# RFboardLeiden48_V_0_63.net
KiCad netlist of a schematic drawn in EAGLE
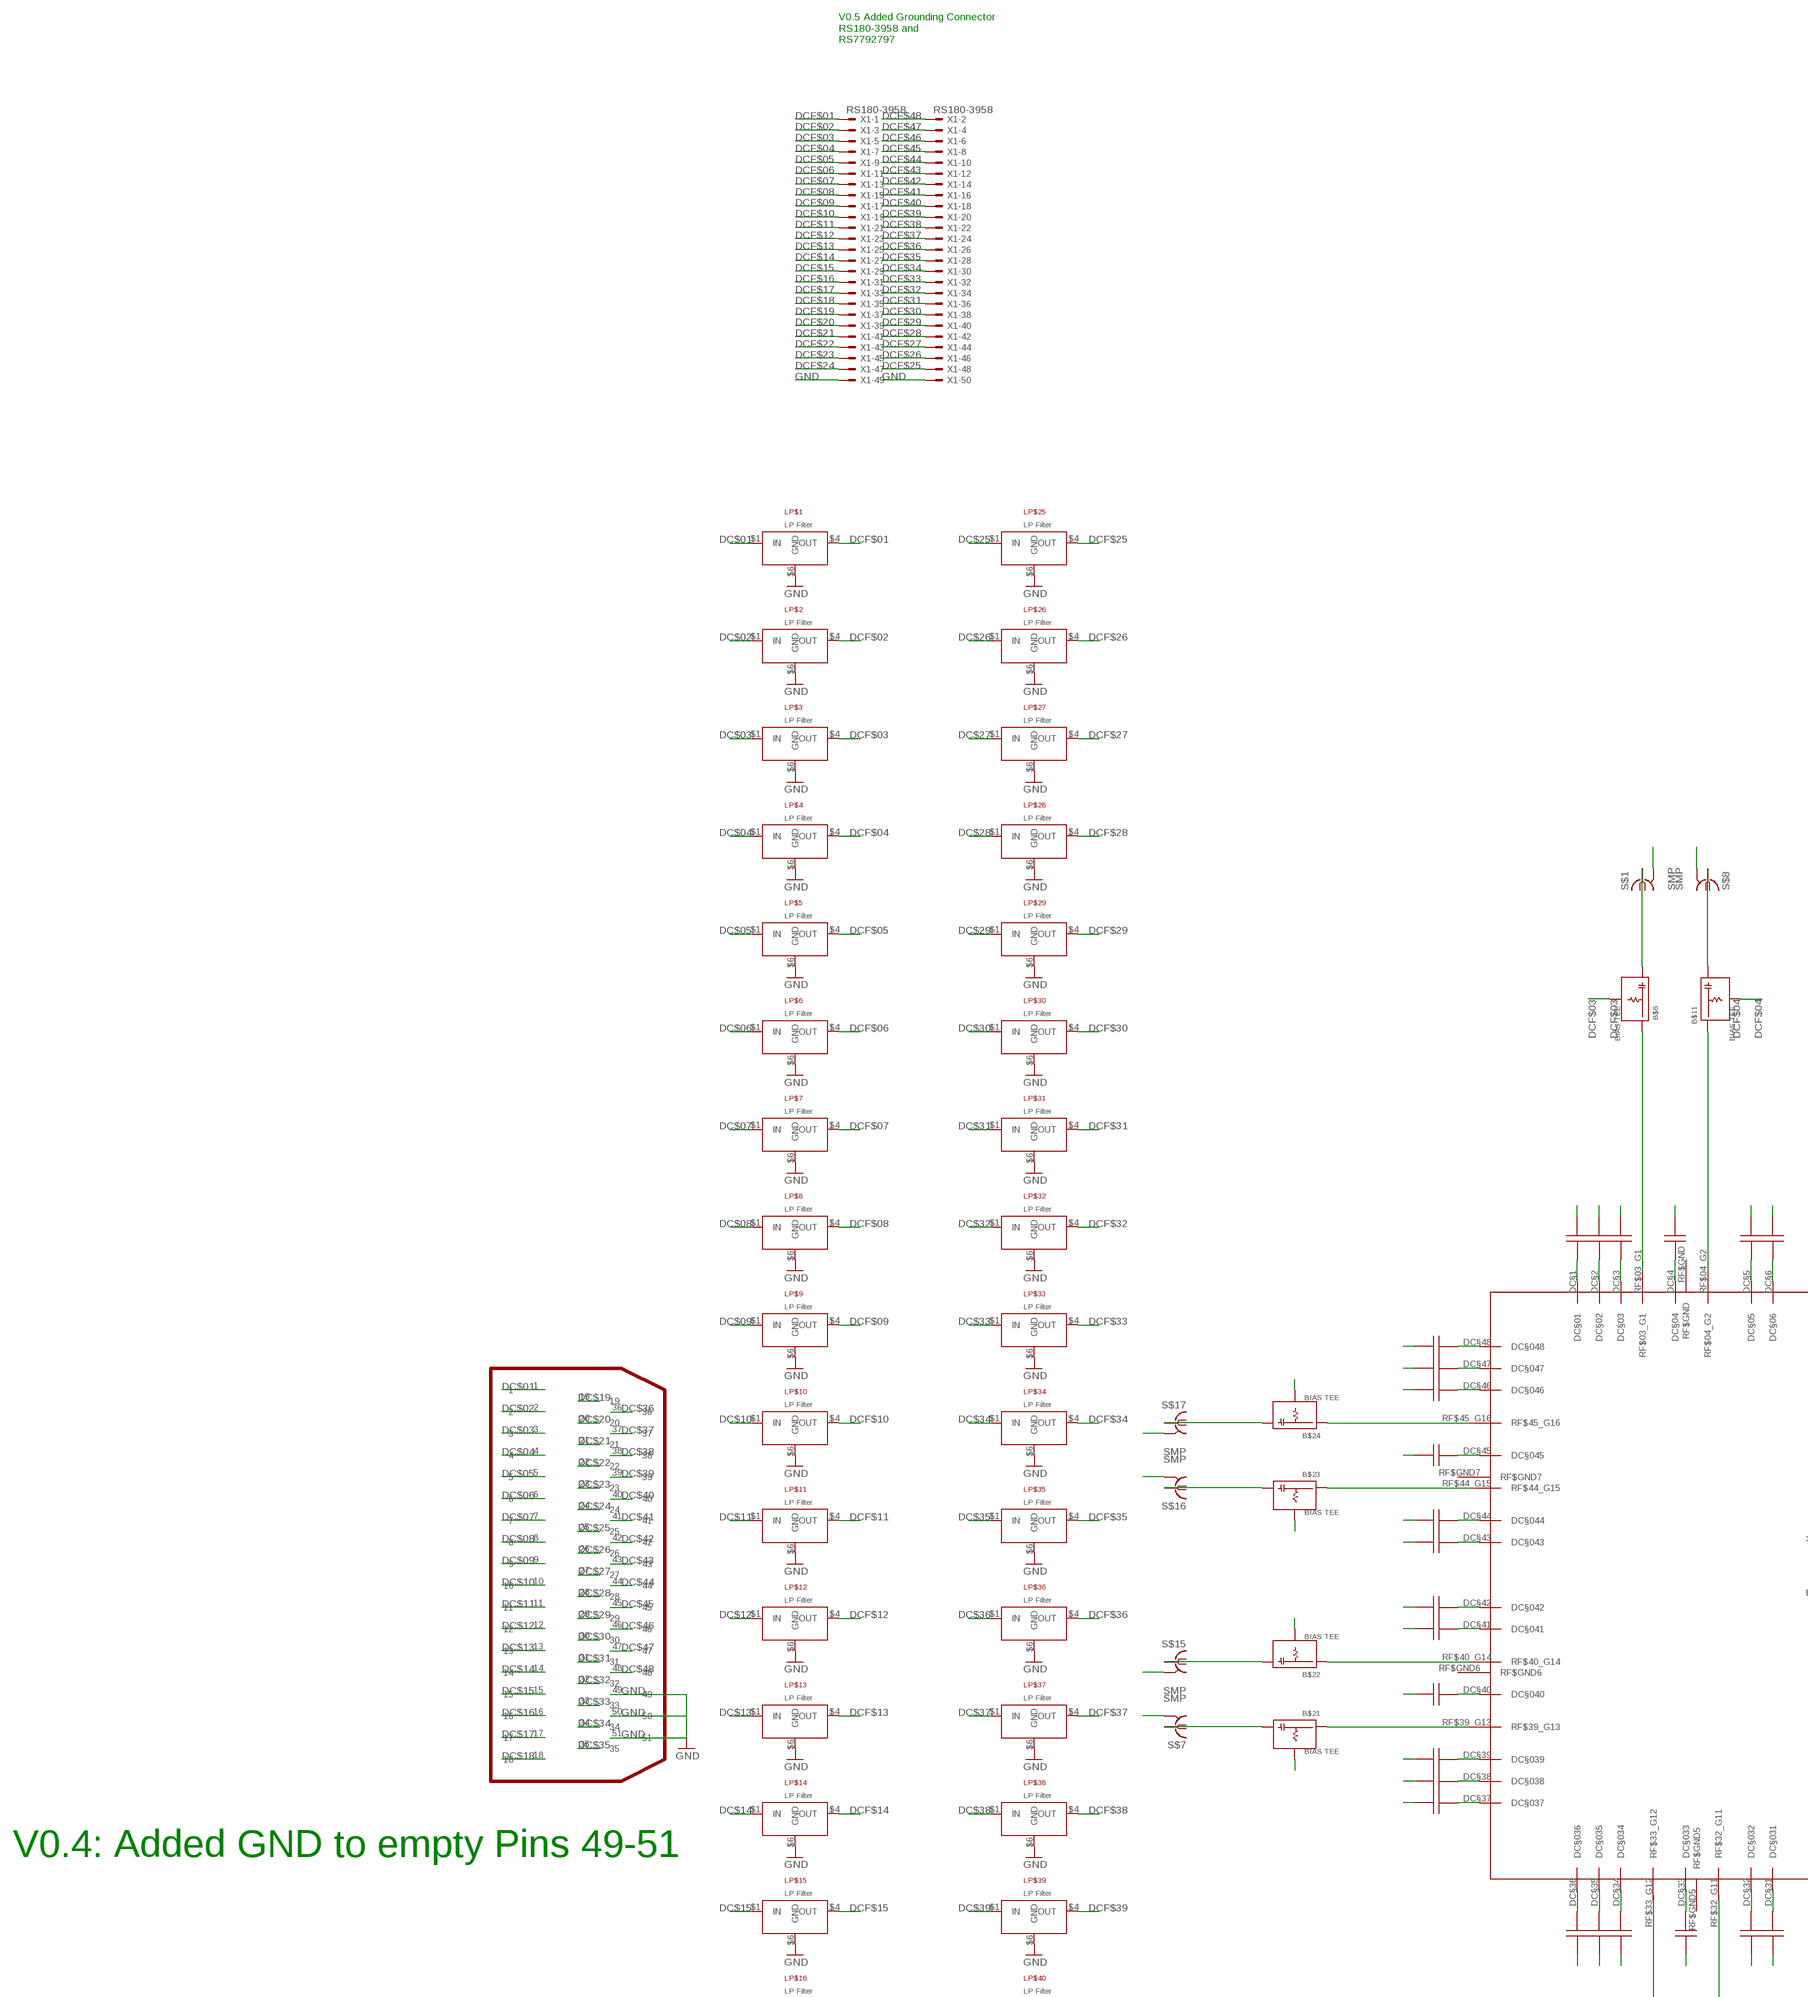
[diagram p0: schematic, sheet 1, part 1 of 3]
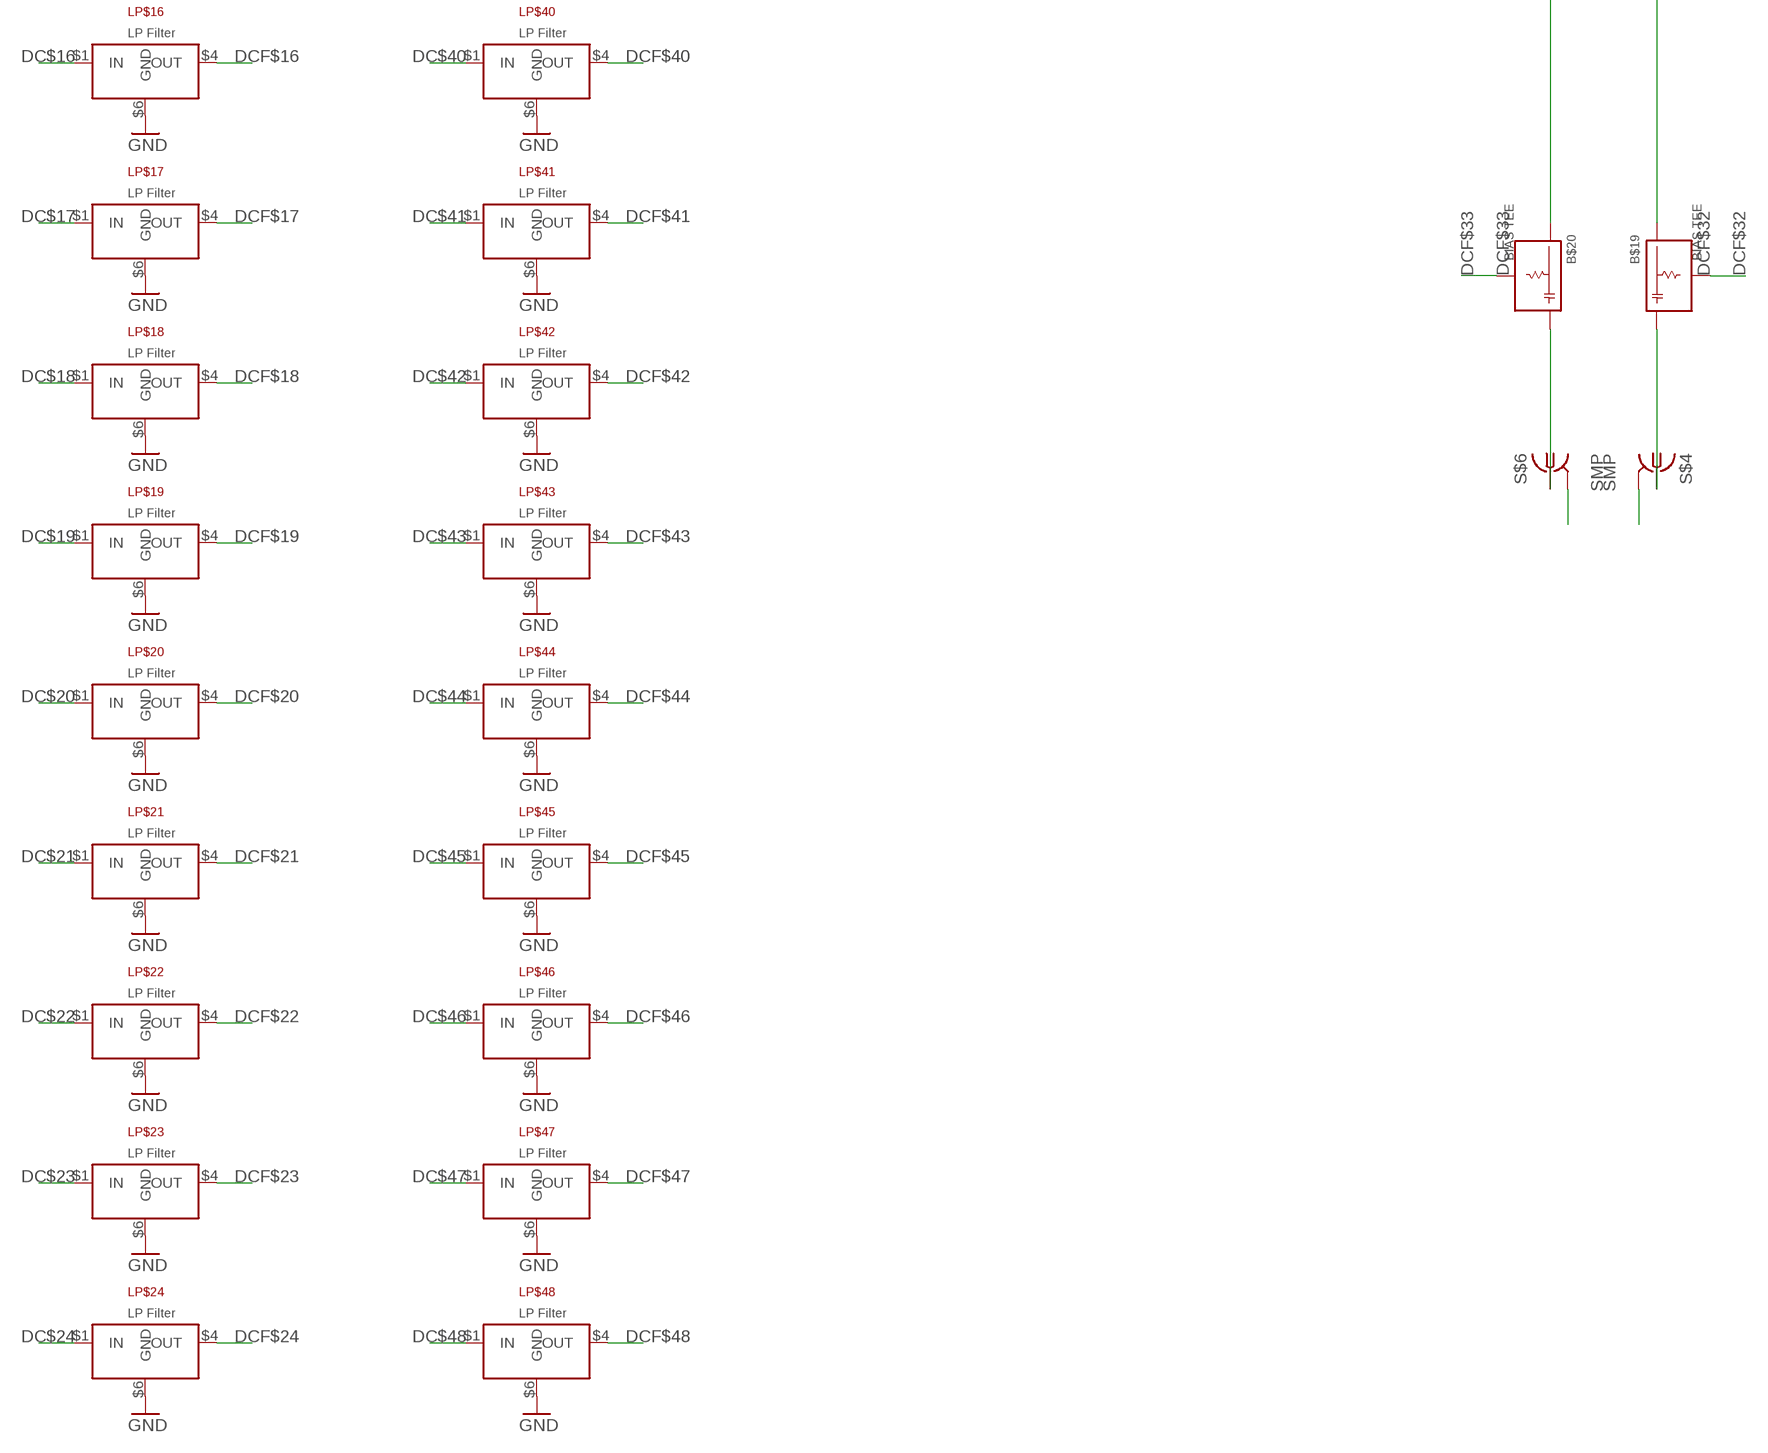
[diagram p1: schematic, sheet 1, part 2 of 3]
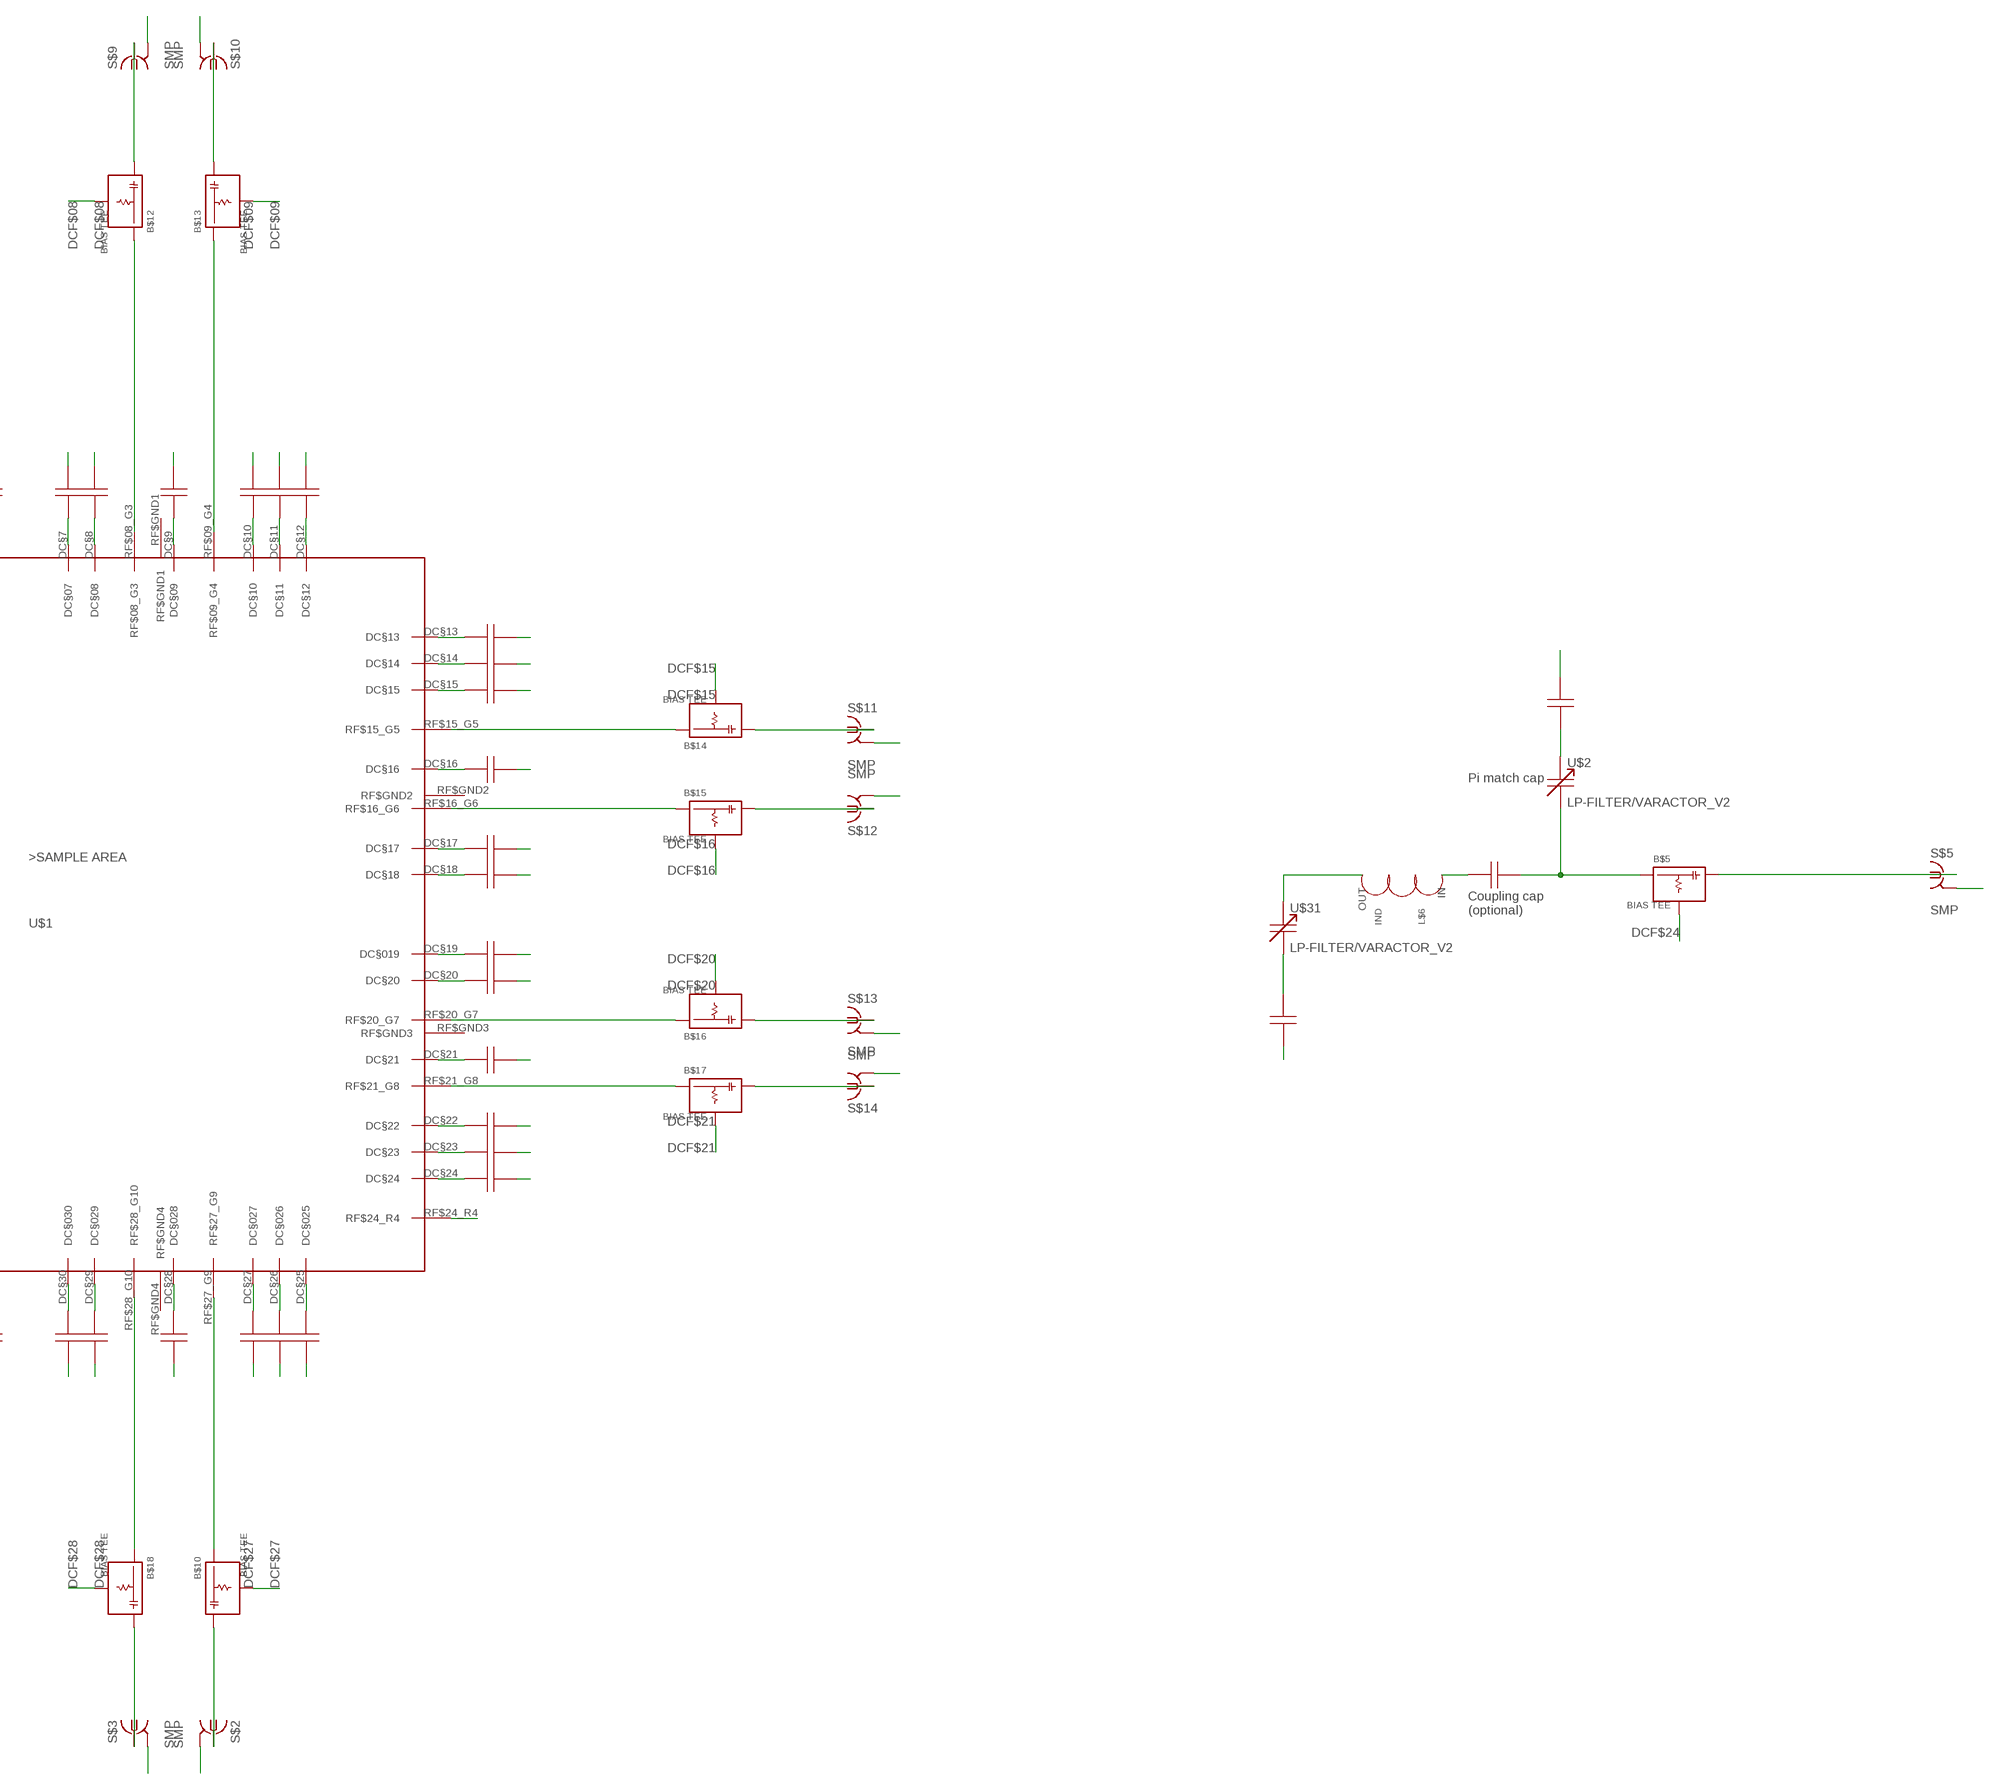
[diagram p2: schematic, sheet 1, part 3 of 3]

(export (version "E")
  (design (tool "Eeschema 10.0.6"))
  (components
    (comp (ref "B$5")
      (value "BIASTEETHINUP")
      (footprint "eagle-import:BIAS_TEE_UP_0603_THIN")
      (libsource (lib "eagle-import") (part "BIASTEETHINUP"))
    )
    (comp (ref "B$6")
      (value "BIASTEEDOWN1")
      (footprint "eagle-import:BIAS_TEE_DOWN_0603")
      (libsource (lib "eagle-import") (part "BIASTEEDOWN1"))
    )
    (comp (ref "B$10")
      (value "BIASTEEDOWN1")
      (footprint "eagle-import:BIAS_TEE_DOWN_0603")
      (libsource (lib "eagle-import") (part "BIASTEEDOWN1"))
    )
    (comp (ref "B$11")
      (value "BIASTEEDOWN1")
      (footprint "eagle-import:BIAS_TEE_DOWN_0603")
      (libsource (lib "eagle-import") (part "BIASTEEDOWN1"))
    )
    (comp (ref "B$12")
      (value "BIASTEEUP1")
      (footprint "eagle-import:BIAS_TEE_UP_0603")
      (libsource (lib "eagle-import") (part "BIASTEEUP1"))
    )
    (comp (ref "B$13")
      (value "BIASTEEUP1")
      (footprint "eagle-import:BIAS_TEE_UP_0603")
      (libsource (lib "eagle-import") (part "BIASTEEUP1"))
    )
    (comp (ref "B$14")
      (value "BIASTEEDOWN1")
      (footprint "eagle-import:BIAS_TEE_DOWN_0603")
      (libsource (lib "eagle-import") (part "BIASTEEDOWN1"))
    )
    (comp (ref "B$15")
      (value "BIASTEEDOWN1")
      (footprint "eagle-import:BIAS_TEE_DOWN_0603")
      (libsource (lib "eagle-import") (part "BIASTEEDOWN1"))
    )
    (comp (ref "B$16")
      (value "BIASTEEUP1")
      (footprint "eagle-import:BIAS_TEE_UP_0603")
      (libsource (lib "eagle-import") (part "BIASTEEUP1"))
    )
    (comp (ref "B$17")
      (value "BIASTEEUP1")
      (footprint "eagle-import:BIAS_TEE_UP_0603")
      (libsource (lib "eagle-import") (part "BIASTEEUP1"))
    )
    (comp (ref "B$18")
      (value "BIASTEEDOWN1")
      (footprint "eagle-import:BIAS_TEE_DOWN_0603")
      (libsource (lib "eagle-import") (part "BIASTEEDOWN1"))
    )
    (comp (ref "B$19")
      (value "BIASTEEUP1")
      (footprint "eagle-import:BIAS_TEE_UP_0603")
      (libsource (lib "eagle-import") (part "BIASTEEUP1"))
    )
    (comp (ref "B$20")
      (value "BIASTEEUP1")
      (footprint "eagle-import:BIAS_TEE_UP_0603")
      (libsource (lib "eagle-import") (part "BIASTEEUP1"))
    )
    (comp (ref "B$21")
      (value "BIASTEEDOWN1")
      (footprint "eagle-import:BIAS_TEE_DOWN_0603")
      (libsource (lib "eagle-import") (part "BIASTEEDOWN1"))
    )
    (comp (ref "B$22")
      (value "BIASTEEDOWN1")
      (footprint "eagle-import:BIAS_TEE_DOWN_0603")
      (libsource (lib "eagle-import") (part "BIASTEEDOWN1"))
    )
    (comp (ref "B$23")
      (value "BIASTEEUP1")
      (footprint "eagle-import:BIAS_TEE_UP_0603")
      (libsource (lib "eagle-import") (part "BIASTEEUP1"))
    )
    (comp (ref "B$24")
      (value "BIASTEEUP1")
      (footprint "eagle-import:BIAS_TEE_UP_0603")
      (libsource (lib "eagle-import") (part "BIASTEEUP1"))
    )
    (comp (ref "L$6")
      (value "L_MATCH")
      (footprint "eagle-import:L_MATCH")
      (libsource (lib "eagle-import") (part "L_MATCH"))
    )
    (comp (ref "LP$1")
      (value "LP-FILTER/1-STAGETOP")
      (footprint "eagle-import:LP-FILTER_1_STAGE_OS_0603_TOP")
      (libsource (lib "eagle-import") (part "LP-FILTER/1-STAGETOP"))
    )
    (comp (ref "LP$2")
      (value "LP-FILTER/1-STAGETOP")
      (footprint "eagle-import:LP-FILTER_1_STAGE_OS_0603_TOP")
      (libsource (lib "eagle-import") (part "LP-FILTER/1-STAGETOP"))
    )
    (comp (ref "LP$3")
      (value "LP-FILTER/1-STAGETOP")
      (footprint "eagle-import:LP-FILTER_1_STAGE_OS_0603_TOP")
      (libsource (lib "eagle-import") (part "LP-FILTER/1-STAGETOP"))
    )
    (comp (ref "LP$4")
      (value "LP-FILTER/1-STAGETOP")
      (footprint "eagle-import:LP-FILTER_1_STAGE_OS_0603_TOP")
      (libsource (lib "eagle-import") (part "LP-FILTER/1-STAGETOP"))
    )
    (comp (ref "LP$5")
      (value "LP-FILTER/1-STAGETOP")
      (footprint "eagle-import:LP-FILTER_1_STAGE_OS_0603_TOP")
      (libsource (lib "eagle-import") (part "LP-FILTER/1-STAGETOP"))
    )
    (comp (ref "LP$6")
      (value "LP-FILTER/1-STAGETOP")
      (footprint "eagle-import:LP-FILTER_1_STAGE_OS_0603_TOP")
      (libsource (lib "eagle-import") (part "LP-FILTER/1-STAGETOP"))
    )
    (comp (ref "LP$7")
      (value "LP-FILTER/1-STAGETOP")
      (footprint "eagle-import:LP-FILTER_1_STAGE_OS_0603_TOP")
      (libsource (lib "eagle-import") (part "LP-FILTER/1-STAGETOP"))
    )
    (comp (ref "LP$8")
      (value "LP-FILTER/1-STAGETOP")
      (footprint "eagle-import:LP-FILTER_1_STAGE_OS_0603_TOP")
      (libsource (lib "eagle-import") (part "LP-FILTER/1-STAGETOP"))
    )
    (comp (ref "LP$9")
      (value "LP-FILTER/1-STAGETOP")
      (footprint "eagle-import:LP-FILTER_1_STAGE_OS_0603_TOP")
      (libsource (lib "eagle-import") (part "LP-FILTER/1-STAGETOP"))
    )
    (comp (ref "LP$10")
      (value "LP-FILTER/1-STAGETOP")
      (footprint "eagle-import:LP-FILTER_1_STAGE_OS_0603_TOP")
      (libsource (lib "eagle-import") (part "LP-FILTER/1-STAGETOP"))
    )
    (comp (ref "LP$11")
      (value "LP-FILTER/1-STAGETOP")
      (footprint "eagle-import:LP-FILTER_1_STAGE_OS_0603_TOP")
      (libsource (lib "eagle-import") (part "LP-FILTER/1-STAGETOP"))
    )
    (comp (ref "LP$12")
      (value "LP-FILTER/1-STAGETOP")
      (footprint "eagle-import:LP-FILTER_1_STAGE_OS_0603_TOP")
      (libsource (lib "eagle-import") (part "LP-FILTER/1-STAGETOP"))
    )
    (comp (ref "LP$13")
      (value "LP-FILTER/1-STAGETOP")
      (footprint "eagle-import:LP-FILTER_1_STAGE_OS_0603_TOP")
      (libsource (lib "eagle-import") (part "LP-FILTER/1-STAGETOP"))
    )
    (comp (ref "LP$14")
      (value "LP-FILTER/1-STAGETOP")
      (footprint "eagle-import:LP-FILTER_1_STAGE_OS_0603_TOP")
      (libsource (lib "eagle-import") (part "LP-FILTER/1-STAGETOP"))
    )
    (comp (ref "LP$15")
      (value "LP-FILTER/1-STAGETOP")
      (footprint "eagle-import:LP-FILTER_1_STAGE_OS_0603_TOP")
      (libsource (lib "eagle-import") (part "LP-FILTER/1-STAGETOP"))
    )
    (comp (ref "LP$16")
      (value "LP-FILTER/1-STAGETOP")
      (footprint "eagle-import:LP-FILTER_1_STAGE_OS_0603_TOP")
      (libsource (lib "eagle-import") (part "LP-FILTER/1-STAGETOP"))
    )
    (comp (ref "LP$17")
      (value "LP-FILTER/1-STAGETOP")
      (footprint "eagle-import:LP-FILTER_1_STAGE_OS_0603_TOP")
      (libsource (lib "eagle-import") (part "LP-FILTER/1-STAGETOP"))
    )
    (comp (ref "LP$18")
      (value "LP-FILTER/1-STAGETOP")
      (footprint "eagle-import:LP-FILTER_1_STAGE_OS_0603_TOP")
      (libsource (lib "eagle-import") (part "LP-FILTER/1-STAGETOP"))
    )
    (comp (ref "LP$19")
      (value "LP-FILTER/1-STAGETOP")
      (footprint "eagle-import:LP-FILTER_1_STAGE_OS_0603_TOP")
      (libsource (lib "eagle-import") (part "LP-FILTER/1-STAGETOP"))
    )
    (comp (ref "LP$20")
      (value "LP-FILTER/1-STAGETOP")
      (footprint "eagle-import:LP-FILTER_1_STAGE_OS_0603_TOP")
      (libsource (lib "eagle-import") (part "LP-FILTER/1-STAGETOP"))
    )
    (comp (ref "LP$21")
      (value "LP-FILTER/1-STAGETOP")
      (footprint "eagle-import:LP-FILTER_1_STAGE_OS_0603_TOP")
      (libsource (lib "eagle-import") (part "LP-FILTER/1-STAGETOP"))
    )
    (comp (ref "LP$22")
      (value "LP-FILTER/1-STAGETOP")
      (footprint "eagle-import:LP-FILTER_1_STAGE_OS_0603_TOP")
      (libsource (lib "eagle-import") (part "LP-FILTER/1-STAGETOP"))
    )
    (comp (ref "LP$23")
      (value "LP-FILTER/1-STAGETOP")
      (footprint "eagle-import:LP-FILTER_1_STAGE_OS_0603_TOP")
      (libsource (lib "eagle-import") (part "LP-FILTER/1-STAGETOP"))
    )
    (comp (ref "LP$24")
      (value "LP-FILTER/1-STAGETOP")
      (footprint "eagle-import:LP-FILTER_1_STAGE_OS_0603_TOP")
      (libsource (lib "eagle-import") (part "LP-FILTER/1-STAGETOP"))
    )
    (comp (ref "LP$25")
      (value "LP-FILTER/1-STAGETOP")
      (footprint "eagle-import:LP-FILTER_1_STAGE_OS_0603_TOP")
      (libsource (lib "eagle-import") (part "LP-FILTER/1-STAGETOP"))
    )
    (comp (ref "LP$26")
      (value "LP-FILTER/1-STAGETOP")
      (footprint "eagle-import:LP-FILTER_1_STAGE_OS_0603_TOP")
      (libsource (lib "eagle-import") (part "LP-FILTER/1-STAGETOP"))
    )
    (comp (ref "LP$27")
      (value "LP-FILTER/1-STAGETOP")
      (footprint "eagle-import:LP-FILTER_1_STAGE_OS_0603_TOP")
      (libsource (lib "eagle-import") (part "LP-FILTER/1-STAGETOP"))
    )
    (comp (ref "LP$28")
      (value "LP-FILTER/1-STAGETOP")
      (footprint "eagle-import:LP-FILTER_1_STAGE_OS_0603_TOP")
      (libsource (lib "eagle-import") (part "LP-FILTER/1-STAGETOP"))
    )
    (comp (ref "LP$29")
      (value "LP-FILTER/1-STAGETOP")
      (footprint "eagle-import:LP-FILTER_1_STAGE_OS_0603_TOP")
      (libsource (lib "eagle-import") (part "LP-FILTER/1-STAGETOP"))
    )
    (comp (ref "LP$30")
      (value "LP-FILTER/1-STAGETOP")
      (footprint "eagle-import:LP-FILTER_1_STAGE_OS_0603_TOP")
      (libsource (lib "eagle-import") (part "LP-FILTER/1-STAGETOP"))
    )
    (comp (ref "LP$31")
      (value "LP-FILTER/1-STAGETOP")
      (footprint "eagle-import:LP-FILTER_1_STAGE_OS_0603_TOP")
      (libsource (lib "eagle-import") (part "LP-FILTER/1-STAGETOP"))
    )
    (comp (ref "LP$32")
      (value "LP-FILTER/1-STAGETOP")
      (footprint "eagle-import:LP-FILTER_1_STAGE_OS_0603_TOP")
      (libsource (lib "eagle-import") (part "LP-FILTER/1-STAGETOP"))
    )
    (comp (ref "LP$33")
      (value "LP-FILTER/1-STAGETOP")
      (footprint "eagle-import:LP-FILTER_1_STAGE_OS_0603_TOP")
      (libsource (lib "eagle-import") (part "LP-FILTER/1-STAGETOP"))
    )
    (comp (ref "LP$34")
      (value "LP-FILTER/1-STAGETOP")
      (footprint "eagle-import:LP-FILTER_1_STAGE_OS_0603_TOP")
      (libsource (lib "eagle-import") (part "LP-FILTER/1-STAGETOP"))
    )
    (comp (ref "LP$35")
      (value "LP-FILTER/1-STAGETOP")
      (footprint "eagle-import:LP-FILTER_1_STAGE_OS_0603_TOP")
      (libsource (lib "eagle-import") (part "LP-FILTER/1-STAGETOP"))
    )
    (comp (ref "LP$36")
      (value "LP-FILTER/1-STAGETOP")
      (footprint "eagle-import:LP-FILTER_1_STAGE_OS_0603_TOP")
      (libsource (lib "eagle-import") (part "LP-FILTER/1-STAGETOP"))
    )
    (comp (ref "LP$37")
      (value "LP-FILTER/1-STAGETOP")
      (footprint "eagle-import:LP-FILTER_1_STAGE_OS_0603_TOP")
      (libsource (lib "eagle-import") (part "LP-FILTER/1-STAGETOP"))
    )
    (comp (ref "LP$38")
      (value "LP-FILTER/1-STAGETOP")
      (footprint "eagle-import:LP-FILTER_1_STAGE_OS_0603_TOP")
      (libsource (lib "eagle-import") (part "LP-FILTER/1-STAGETOP"))
    )
    (comp (ref "LP$39")
      (value "LP-FILTER/1-STAGETOP")
      (footprint "eagle-import:LP-FILTER_1_STAGE_OS_0603_TOP")
      (libsource (lib "eagle-import") (part "LP-FILTER/1-STAGETOP"))
    )
    (comp (ref "LP$40")
      (value "LP-FILTER/1-STAGETOP")
      (footprint "eagle-import:LP-FILTER_1_STAGE_OS_0603_TOP")
      (libsource (lib "eagle-import") (part "LP-FILTER/1-STAGETOP"))
    )
    (comp (ref "LP$41")
      (value "LP-FILTER/1-STAGETOP")
      (footprint "eagle-import:LP-FILTER_1_STAGE_OS_0603_TOP")
      (libsource (lib "eagle-import") (part "LP-FILTER/1-STAGETOP"))
    )
    (comp (ref "LP$42")
      (value "LP-FILTER/1-STAGETOP")
      (footprint "eagle-import:LP-FILTER_1_STAGE_OS_0603_TOP")
      (libsource (lib "eagle-import") (part "LP-FILTER/1-STAGETOP"))
    )
    (comp (ref "LP$43")
      (value "LP-FILTER/1-STAGETOP")
      (footprint "eagle-import:LP-FILTER_1_STAGE_OS_0603_TOP")
      (libsource (lib "eagle-import") (part "LP-FILTER/1-STAGETOP"))
    )
    (comp (ref "LP$44")
      (value "LP-FILTER/1-STAGETOP")
      (footprint "eagle-import:LP-FILTER_1_STAGE_OS_0603_TOP")
      (libsource (lib "eagle-import") (part "LP-FILTER/1-STAGETOP"))
    )
    (comp (ref "LP$45")
      (value "LP-FILTER/1-STAGETOP")
      (footprint "eagle-import:LP-FILTER_1_STAGE_OS_0603_TOP")
      (libsource (lib "eagle-import") (part "LP-FILTER/1-STAGETOP"))
    )
    (comp (ref "LP$46")
      (value "LP-FILTER/1-STAGETOP")
      (footprint "eagle-import:LP-FILTER_1_STAGE_OS_0603_TOP")
      (libsource (lib "eagle-import") (part "LP-FILTER/1-STAGETOP"))
    )
    (comp (ref "LP$47")
      (value "LP-FILTER/1-STAGETOP")
      (footprint "eagle-import:LP-FILTER_1_STAGE_OS_0603_TOP")
      (libsource (lib "eagle-import") (part "LP-FILTER/1-STAGETOP"))
    )
    (comp (ref "LP$48")
      (value "LP-FILTER/1-STAGETOP")
      (footprint "eagle-import:LP-FILTER_1_STAGE_OS_0603_TOP")
      (libsource (lib "eagle-import") (part "LP-FILTER/1-STAGETOP"))
    )
    (comp (ref "S$1")
      (value "MC-921WIDE")
      (footprint "eagle-import:SMP_STRAIGHT_MINI_WIDE")
      (libsource (lib "eagle-import") (part "MC-921WIDE"))
    )
    (comp (ref "S$2")
      (value "MC-921WIDE")
      (footprint "eagle-import:SMP_STRAIGHT_MINI_WIDE")
      (libsource (lib "eagle-import") (part "MC-921WIDE"))
    )
    (comp (ref "S$3")
      (value "MC-921WIDE")
      (footprint "eagle-import:SMP_STRAIGHT_MINI_WIDE")
      (libsource (lib "eagle-import") (part "MC-921WIDE"))
    )
    (comp (ref "S$4")
      (value "MC-921WIDE")
      (footprint "eagle-import:SMP_STRAIGHT_MINI_WIDE")
      (libsource (lib "eagle-import") (part "MC-921WIDE"))
    )
    (comp (ref "S$5")
      (value "MC-921")
      (footprint "eagle-import:SMP_STRAIGHT_MINI_WIDE_V1_01_ROUND")
      (libsource (lib "eagle-import") (part "MC-921"))
    )
    (comp (ref "S$6")
      (value "MC-921WIDE")
      (footprint "eagle-import:SMP_STRAIGHT_MINI_WIDE")
      (libsource (lib "eagle-import") (part "MC-921WIDE"))
    )
    (comp (ref "S$7")
      (value "MC-921WIDE")
      (footprint "eagle-import:SMP_STRAIGHT_MINI_WIDE")
      (libsource (lib "eagle-import") (part "MC-921WIDE"))
    )
    (comp (ref "S$8")
      (value "MC-921WIDE")
      (footprint "eagle-import:SMP_STRAIGHT_MINI_WIDE")
      (libsource (lib "eagle-import") (part "MC-921WIDE"))
    )
    (comp (ref "S$9")
      (value "MC-921WIDE")
      (footprint "eagle-import:SMP_STRAIGHT_MINI_WIDE")
      (libsource (lib "eagle-import") (part "MC-921WIDE"))
    )
    (comp (ref "S$10")
      (value "MC-921WIDE")
      (footprint "eagle-import:SMP_STRAIGHT_MINI_WIDE")
      (libsource (lib "eagle-import") (part "MC-921WIDE"))
    )
    (comp (ref "S$11")
      (value "MC-921WIDE")
      (footprint "eagle-import:SMP_STRAIGHT_MINI_WIDE")
      (libsource (lib "eagle-import") (part "MC-921WIDE"))
    )
    (comp (ref "S$12")
      (value "MC-921WIDE")
      (footprint "eagle-import:SMP_STRAIGHT_MINI_WIDE")
      (libsource (lib "eagle-import") (part "MC-921WIDE"))
    )
    (comp (ref "S$13")
      (value "MC-921WIDE")
      (footprint "eagle-import:SMP_STRAIGHT_MINI_WIDE")
      (libsource (lib "eagle-import") (part "MC-921WIDE"))
    )
    (comp (ref "S$14")
      (value "MC-921WIDE")
      (footprint "eagle-import:SMP_STRAIGHT_MINI_WIDE")
      (libsource (lib "eagle-import") (part "MC-921WIDE"))
    )
    (comp (ref "S$15")
      (value "MC-921WIDE")
      (footprint "eagle-import:SMP_STRAIGHT_MINI_WIDE")
      (libsource (lib "eagle-import") (part "MC-921WIDE"))
    )
    (comp (ref "S$16")
      (value "MC-921WIDE")
      (footprint "eagle-import:SMP_STRAIGHT_MINI_WIDE")
      (libsource (lib "eagle-import") (part "MC-921WIDE"))
    )
    (comp (ref "S$17")
      (value "MC-921WIDE")
      (footprint "eagle-import:SMP_STRAIGHT_MINI_WIDE")
      (libsource (lib "eagle-import") (part "MC-921WIDE"))
    )
    (comp (ref "U$1")
      (value "48DC+24RF_V4.0")
      (footprint "eagle-import:48DC+24RF_V4.0")
      (libsource (lib "eagle-import") (part "48DC+24RF_V4.0"))
    )
    (comp (ref "U$2")
      (value "LP-FILTER/VARACTOR_V2")
      (footprint "eagle-import:LP-FILTER_VARACTOR_V2")
      (libsource (lib "eagle-import") (part "LP-FILTER/VARACTOR_V2"))
    )
    (comp (ref "U$3")
      (value "LP-FILTER/CAPACITOR/0603NORMAL")
      (footprint "eagle-import:LP-FILTER_CAPACITOR_0603_BOTTOM_V2")
      (libsource (lib "eagle-import") (part "LP-FILTER/CAPACITOR/0603NORMAL"))
    )
    (comp (ref "U$25")
      (value "51_PIN_M83513/11-G")
      (footprint "eagle-import:51_PIN_M83513_11-G")
      (libsource (lib "eagle-import") (part "51_PIN_M83513/11-G"))
    )
    (comp (ref "U$31")
      (value "LP-FILTER/VARACTOR_V2")
      (footprint "eagle-import:LP-FILTER_VARACTOR_V2")
      (libsource (lib "eagle-import") (part "LP-FILTER/VARACTOR_V2"))
    )
    (comp (ref "U$32")
      (value "LP-FILTER/CAPACITOR/0603NORMAL")
      (footprint "eagle-import:LP-FILTER_CAPACITOR_0603_BOTTOM_V2")
      (libsource (lib "eagle-import") (part "LP-FILTER/CAPACITOR/0603NORMAL"))
    )
    (comp (ref "U$33")
      (value "LP-FILTER/CAPACITOR/0603THIN")
      (footprint "eagle-import:LP-FILTER_CAPACITOR_0603_BOTTOM")
      (libsource (lib "eagle-import") (part "LP-FILTER/CAPACITOR/0603THIN"))
    )
    (comp (ref "U$42")
      (value "LP-FILTER/CAPACITOR/0603THIN")
      (footprint "eagle-import:LP-FILTER_CAPACITOR_0603_BOTTOM")
      (libsource (lib "eagle-import") (part "LP-FILTER/CAPACITOR/0603THIN"))
    )
    (comp (ref "U$43")
      (value "LP-FILTER/CAPACITOR/0603THIN")
      (footprint "eagle-import:LP-FILTER_CAPACITOR_0603_BOTTOM")
      (libsource (lib "eagle-import") (part "LP-FILTER/CAPACITOR/0603THIN"))
    )
    (comp (ref "U$44")
      (value "LP-FILTER/CAPACITOR/0603THIN")
      (footprint "eagle-import:LP-FILTER_CAPACITOR_0603_BOTTOM")
      (libsource (lib "eagle-import") (part "LP-FILTER/CAPACITOR/0603THIN"))
    )
    (comp (ref "U$45")
      (value "LP-FILTER/CAPACITOR/0603THIN")
      (footprint "eagle-import:LP-FILTER_CAPACITOR_0603_BOTTOM")
      (libsource (lib "eagle-import") (part "LP-FILTER/CAPACITOR/0603THIN"))
    )
    (comp (ref "U$46")
      (value "LP-FILTER/CAPACITOR/0603THIN")
      (footprint "eagle-import:LP-FILTER_CAPACITOR_0603_BOTTOM")
      (libsource (lib "eagle-import") (part "LP-FILTER/CAPACITOR/0603THIN"))
    )
    (comp (ref "U$47")
      (value "LP-FILTER/CAPACITOR/0603THIN")
      (footprint "eagle-import:LP-FILTER_CAPACITOR_0603_BOTTOM")
      (libsource (lib "eagle-import") (part "LP-FILTER/CAPACITOR/0603THIN"))
    )
    (comp (ref "U$48")
      (value "LP-FILTER/CAPACITOR/0603THIN")
      (footprint "eagle-import:LP-FILTER_CAPACITOR_0603_BOTTOM")
      (libsource (lib "eagle-import") (part "LP-FILTER/CAPACITOR/0603THIN"))
    )
    (comp (ref "U$49")
      (value "LP-FILTER/CAPACITOR/0603THIN")
      (footprint "eagle-import:LP-FILTER_CAPACITOR_0603_BOTTOM")
      (libsource (lib "eagle-import") (part "LP-FILTER/CAPACITOR/0603THIN"))
    )
    (comp (ref "U$50")
      (value "LP-FILTER/CAPACITOR/0603THIN")
      (footprint "eagle-import:LP-FILTER_CAPACITOR_0603_BOTTOM")
      (libsource (lib "eagle-import") (part "LP-FILTER/CAPACITOR/0603THIN"))
    )
    (comp (ref "U$51")
      (value "LP-FILTER/CAPACITOR/0603THIN")
      (footprint "eagle-import:LP-FILTER_CAPACITOR_0603_BOTTOM")
      (libsource (lib "eagle-import") (part "LP-FILTER/CAPACITOR/0603THIN"))
    )
    (comp (ref "U$52")
      (value "LP-FILTER/CAPACITOR/0603THIN")
      (footprint "eagle-import:LP-FILTER_CAPACITOR_0603_BOTTOM")
      (libsource (lib "eagle-import") (part "LP-FILTER/CAPACITOR/0603THIN"))
    )
    (comp (ref "U$53")
      (value "LP-FILTER/CAPACITOR/0603THIN")
      (footprint "eagle-import:LP-FILTER_CAPACITOR_0603_BOTTOM")
      (libsource (lib "eagle-import") (part "LP-FILTER/CAPACITOR/0603THIN"))
    )
    (comp (ref "U$54")
      (value "LP-FILTER/CAPACITOR/0603THIN")
      (footprint "eagle-import:LP-FILTER_CAPACITOR_0603_BOTTOM")
      (libsource (lib "eagle-import") (part "LP-FILTER/CAPACITOR/0603THIN"))
    )
    (comp (ref "U$55")
      (value "LP-FILTER/CAPACITOR/0603THIN")
      (footprint "eagle-import:LP-FILTER_CAPACITOR_0603_BOTTOM")
      (libsource (lib "eagle-import") (part "LP-FILTER/CAPACITOR/0603THIN"))
    )
    (comp (ref "U$56")
      (value "LP-FILTER/CAPACITOR/0603THIN")
      (footprint "eagle-import:LP-FILTER_CAPACITOR_0603_BOTTOM")
      (libsource (lib "eagle-import") (part "LP-FILTER/CAPACITOR/0603THIN"))
    )
    (comp (ref "U$57")
      (value "LP-FILTER/CAPACITOR/0603THIN")
      (footprint "eagle-import:LP-FILTER_CAPACITOR_0603_BOTTOM")
      (libsource (lib "eagle-import") (part "LP-FILTER/CAPACITOR/0603THIN"))
    )
    (comp (ref "U$58")
      (value "LP-FILTER/CAPACITOR/0603THIN")
      (footprint "eagle-import:LP-FILTER_CAPACITOR_0603_BOTTOM")
      (libsource (lib "eagle-import") (part "LP-FILTER/CAPACITOR/0603THIN"))
    )
    (comp (ref "U$59")
      (value "LP-FILTER/CAPACITOR/0603THIN")
      (footprint "eagle-import:LP-FILTER_CAPACITOR_0603_BOTTOM")
      (libsource (lib "eagle-import") (part "LP-FILTER/CAPACITOR/0603THIN"))
    )
    (comp (ref "U$60")
      (value "LP-FILTER/CAPACITOR/0603THIN")
      (footprint "eagle-import:LP-FILTER_CAPACITOR_0603_BOTTOM")
      (libsource (lib "eagle-import") (part "LP-FILTER/CAPACITOR/0603THIN"))
    )
    (comp (ref "U$61")
      (value "LP-FILTER/CAPACITOR/0603THIN")
      (footprint "eagle-import:LP-FILTER_CAPACITOR_0603_BOTTOM")
      (libsource (lib "eagle-import") (part "LP-FILTER/CAPACITOR/0603THIN"))
    )
    (comp (ref "U$62")
      (value "LP-FILTER/CAPACITOR/0603THIN")
      (footprint "eagle-import:LP-FILTER_CAPACITOR_0603_BOTTOM")
      (libsource (lib "eagle-import") (part "LP-FILTER/CAPACITOR/0603THIN"))
    )
    (comp (ref "U$63")
      (value "LP-FILTER/CAPACITOR/0603THIN")
      (footprint "eagle-import:LP-FILTER_CAPACITOR_0603_BOTTOM")
      (libsource (lib "eagle-import") (part "LP-FILTER/CAPACITOR/0603THIN"))
    )
    (comp (ref "U$64")
      (value "LP-FILTER/CAPACITOR/0603THIN")
      (footprint "eagle-import:LP-FILTER_CAPACITOR_0603_BOTTOM")
      (libsource (lib "eagle-import") (part "LP-FILTER/CAPACITOR/0603THIN"))
    )
    (comp (ref "U$65")
      (value "LP-FILTER/CAPACITOR/0603THIN")
      (footprint "eagle-import:LP-FILTER_CAPACITOR_0603_BOTTOM")
      (libsource (lib "eagle-import") (part "LP-FILTER/CAPACITOR/0603THIN"))
    )
    (comp (ref "U$66")
      (value "LP-FILTER/CAPACITOR/0603THIN")
      (footprint "eagle-import:LP-FILTER_CAPACITOR_0603_BOTTOM")
      (libsource (lib "eagle-import") (part "LP-FILTER/CAPACITOR/0603THIN"))
    )
    (comp (ref "U$67")
      (value "LP-FILTER/CAPACITOR/0603THIN")
      (footprint "eagle-import:LP-FILTER_CAPACITOR_0603_BOTTOM")
      (libsource (lib "eagle-import") (part "LP-FILTER/CAPACITOR/0603THIN"))
    )
    (comp (ref "U$68")
      (value "LP-FILTER/CAPACITOR/0603THIN")
      (footprint "eagle-import:LP-FILTER_CAPACITOR_0603_BOTTOM")
      (libsource (lib "eagle-import") (part "LP-FILTER/CAPACITOR/0603THIN"))
    )
    (comp (ref "U$69")
      (value "LP-FILTER/CAPACITOR/0603THIN")
      (footprint "eagle-import:LP-FILTER_CAPACITOR_0603_BOTTOM")
      (libsource (lib "eagle-import") (part "LP-FILTER/CAPACITOR/0603THIN"))
    )
    (comp (ref "U$70")
      (value "LP-FILTER/CAPACITOR/0603THIN")
      (footprint "eagle-import:LP-FILTER_CAPACITOR_0603_BOTTOM")
      (libsource (lib "eagle-import") (part "LP-FILTER/CAPACITOR/0603THIN"))
    )
    (comp (ref "U$71")
      (value "LP-FILTER/CAPACITOR/0603THIN")
      (footprint "eagle-import:LP-FILTER_CAPACITOR_0603_BOTTOM")
      (libsource (lib "eagle-import") (part "LP-FILTER/CAPACITOR/0603THIN"))
    )
    (comp (ref "U$72")
      (value "LP-FILTER/CAPACITOR/0603THIN")
      (footprint "eagle-import:LP-FILTER_CAPACITOR_0603_BOTTOM")
      (libsource (lib "eagle-import") (part "LP-FILTER/CAPACITOR/0603THIN"))
    )
    (comp (ref "U$73")
      (value "LP-FILTER/CAPACITOR/0603THIN")
      (footprint "eagle-import:LP-FILTER_CAPACITOR_0603_BOTTOM")
      (libsource (lib "eagle-import") (part "LP-FILTER/CAPACITOR/0603THIN"))
    )
    (comp (ref "U$74")
      (value "LP-FILTER/CAPACITOR/0603THIN")
      (footprint "eagle-import:LP-FILTER_CAPACITOR_0603_BOTTOM")
      (libsource (lib "eagle-import") (part "LP-FILTER/CAPACITOR/0603THIN"))
    )
    (comp (ref "U$75")
      (value "LP-FILTER/CAPACITOR/0603THIN")
      (footprint "eagle-import:LP-FILTER_CAPACITOR_0603_BOTTOM")
      (libsource (lib "eagle-import") (part "LP-FILTER/CAPACITOR/0603THIN"))
    )
    (comp (ref "U$76")
      (value "LP-FILTER/CAPACITOR/0603THIN")
      (footprint "eagle-import:LP-FILTER_CAPACITOR_0603_BOTTOM")
      (libsource (lib "eagle-import") (part "LP-FILTER/CAPACITOR/0603THIN"))
    )
    (comp (ref "U$77")
      (value "LP-FILTER/CAPACITOR/0603THIN")
      (footprint "eagle-import:LP-FILTER_CAPACITOR_0603_BOTTOM")
      (libsource (lib "eagle-import") (part "LP-FILTER/CAPACITOR/0603THIN"))
    )
    (comp (ref "U$78")
      (value "LP-FILTER/CAPACITOR/0603THIN")
      (footprint "eagle-import:LP-FILTER_CAPACITOR_0603_BOTTOM")
      (libsource (lib "eagle-import") (part "LP-FILTER/CAPACITOR/0603THIN"))
    )
    (comp (ref "U$79")
      (value "LP-FILTER/CAPACITOR/0603THIN")
      (footprint "eagle-import:LP-FILTER_CAPACITOR_0603_BOTTOM")
      (libsource (lib "eagle-import") (part "LP-FILTER/CAPACITOR/0603THIN"))
    )
    (comp (ref "U$80")
      (value "LP-FILTER/CAPACITOR/0603THIN")
      (footprint "eagle-import:LP-FILTER_CAPACITOR_0603_BOTTOM")
      (libsource (lib "eagle-import") (part "LP-FILTER/CAPACITOR/0603THIN"))
    )
    (comp (ref "U$81")
      (value "LP-FILTER/CAPACITOR/0603THIN")
      (footprint "eagle-import:LP-FILTER_CAPACITOR_0603_BOTTOM")
      (libsource (lib "eagle-import") (part "LP-FILTER/CAPACITOR/0603THIN"))
    )
    (comp (ref "U$82")
      (value "LP-FILTER/CAPACITOR/0603THIN")
      (footprint "eagle-import:LP-FILTER_CAPACITOR_0603_BOTTOM")
      (libsource (lib "eagle-import") (part "LP-FILTER/CAPACITOR/0603THIN"))
    )
    (comp (ref "U$83")
      (value "LP-FILTER/CAPACITOR/0603THIN")
      (footprint "eagle-import:LP-FILTER_CAPACITOR_0603_BOTTOM")
      (libsource (lib "eagle-import") (part "LP-FILTER/CAPACITOR/0603THIN"))
    )
    (comp (ref "U$84")
      (value "LP-FILTER/CAPACITOR/0603THIN")
      (footprint "eagle-import:LP-FILTER_CAPACITOR_0603_BOTTOM")
      (libsource (lib "eagle-import") (part "LP-FILTER/CAPACITOR/0603THIN"))
    )
    (comp (ref "U$85")
      (value "LP-FILTER/CAPACITOR/0603THIN")
      (footprint "eagle-import:LP-FILTER_CAPACITOR_0603_BOTTOM")
      (libsource (lib "eagle-import") (part "LP-FILTER/CAPACITOR/0603THIN"))
    )
    (comp (ref "U$86")
      (value "LP-FILTER/CAPACITOR/0603THIN")
      (footprint "eagle-import:LP-FILTER_CAPACITOR_0603_BOTTOM")
      (libsource (lib "eagle-import") (part "LP-FILTER/CAPACITOR/0603THIN"))
    )
    (comp (ref "U$87")
      (value "LP-FILTER/CAPACITOR/0603THIN")
      (footprint "eagle-import:LP-FILTER_CAPACITOR_0603_BOTTOM")
      (libsource (lib "eagle-import") (part "LP-FILTER/CAPACITOR/0603THIN"))
    )
    (comp (ref "U$88")
      (value "LP-FILTER/CAPACITOR/0603THIN")
      (footprint "eagle-import:LP-FILTER_CAPACITOR_0603_BOTTOM")
      (libsource (lib "eagle-import") (part "LP-FILTER/CAPACITOR/0603THIN"))
    )
    (comp (ref "U$89")
      (value "LP-FILTER/CAPACITOR/0603THIN")
      (footprint "eagle-import:LP-FILTER_CAPACITOR_0603_BOTTOM")
      (libsource (lib "eagle-import") (part "LP-FILTER/CAPACITOR/0603THIN"))
    )
    (comp (ref "X1")
      (value "RS180-3958")
      (footprint "eagle-import:SMDSMALL87758-5016")
      (libsource (lib "eagle-import") (part "87758-5016"))
    )
  )
  (nets
    (net (code "1") (name "/DC$01") (class "Default")
      (node (ref "LP$1") (pin "$1") (pinfunction "IN_$1") (pintype "bidirectional"))
      (node (ref "U$25") (pin "1") (pinfunction "1_1") (pintype "bidirectional"))
    )
    (net (code "2") (name "/DC$02") (class "Default")
      (node (ref "LP$2") (pin "$1") (pinfunction "IN_$1") (pintype "bidirectional"))
      (node (ref "U$25") (pin "2") (pinfunction "2_2") (pintype "bidirectional"))
    )
    (net (code "3") (name "/DC$03") (class "Default")
      (node (ref "LP$3") (pin "$1") (pinfunction "IN_$1") (pintype "bidirectional"))
      (node (ref "U$25") (pin "3") (pinfunction "3_3") (pintype "bidirectional"))
    )
    (net (code "4") (name "/DC$04") (class "Default")
      (node (ref "LP$4") (pin "$1") (pinfunction "IN_$1") (pintype "bidirectional"))
      (node (ref "U$25") (pin "4") (pinfunction "4_4") (pintype "bidirectional"))
    )
    (net (code "5") (name "/DC$05") (class "Default")
      (node (ref "LP$5") (pin "$1") (pinfunction "IN_$1") (pintype "bidirectional"))
      (node (ref "U$25") (pin "5") (pinfunction "5_5") (pintype "bidirectional"))
    )
    (net (code "6") (name "/DC$06") (class "Default")
      (node (ref "LP$6") (pin "$1") (pinfunction "IN_$1") (pintype "bidirectional"))
      (node (ref "U$25") (pin "6") (pinfunction "6_6") (pintype "bidirectional"))
    )
    (net (code "7") (name "/DC$07") (class "Default")
      (node (ref "LP$7") (pin "$1") (pinfunction "IN_$1") (pintype "bidirectional"))
      (node (ref "U$25") (pin "7") (pinfunction "7_7") (pintype "bidirectional"))
    )
    (net (code "8") (name "/DC$08") (class "Default")
      (node (ref "LP$8") (pin "$1") (pinfunction "IN_$1") (pintype "bidirectional"))
      (node (ref "U$25") (pin "8") (pinfunction "8_8") (pintype "bidirectional"))
    )
    (net (code "9") (name "/DC$09") (class "Default")
      (node (ref "LP$9") (pin "$1") (pinfunction "IN_$1") (pintype "bidirectional"))
      (node (ref "U$25") (pin "9") (pinfunction "9_9") (pintype "bidirectional"))
    )
    (net (code "10") (name "/DC$10") (class "Default")
      (node (ref "LP$10") (pin "$1") (pinfunction "IN_$1") (pintype "bidirectional"))
      (node (ref "U$25") (pin "10") (pinfunction "10_10") (pintype "bidirectional"))
    )
    (net (code "11") (name "/DC$11") (class "Default")
      (node (ref "LP$11") (pin "$1") (pinfunction "IN_$1") (pintype "bidirectional"))
      (node (ref "U$25") (pin "11") (pinfunction "11_11") (pintype "bidirectional"))
    )
    (net (code "12") (name "/DC$12") (class "Default")
      (node (ref "LP$12") (pin "$1") (pinfunction "IN_$1") (pintype "bidirectional"))
      (node (ref "U$25") (pin "12") (pinfunction "12_12") (pintype "bidirectional"))
    )
    (net (code "13") (name "/DC$13") (class "Default")
      (node (ref "LP$13") (pin "$1") (pinfunction "IN_$1") (pintype "bidirectional"))
      (node (ref "U$25") (pin "13") (pinfunction "13_13") (pintype "bidirectional"))
    )
    (net (code "14") (name "/DC$14") (class "Default")
      (node (ref "LP$14") (pin "$1") (pinfunction "IN_$1") (pintype "bidirectional"))
      (node (ref "U$25") (pin "14") (pinfunction "14_14") (pintype "bidirectional"))
    )
    (net (code "15") (name "/DC$15") (class "Default")
      (node (ref "LP$15") (pin "$1") (pinfunction "IN_$1") (pintype "bidirectional"))
      (node (ref "U$25") (pin "15") (pinfunction "15_15") (pintype "bidirectional"))
    )
    (net (code "16") (name "/DC$16") (class "Default")
      (node (ref "LP$16") (pin "$1") (pinfunction "IN_$1") (pintype "bidirectional"))
      (node (ref "U$25") (pin "16") (pinfunction "16_16") (pintype "bidirectional"))
    )
    (net (code "17") (name "/DC$17") (class "Default")
      (node (ref "LP$17") (pin "$1") (pinfunction "IN_$1") (pintype "bidirectional"))
      (node (ref "U$25") (pin "17") (pinfunction "17_17") (pintype "bidirectional"))
    )
    (net (code "18") (name "/DC$18") (class "Default")
      (node (ref "LP$18") (pin "$1") (pinfunction "IN_$1") (pintype "bidirectional"))
      (node (ref "U$25") (pin "18") (pinfunction "18_18") (pintype "bidirectional"))
    )
    (net (code "19") (name "/DC$19") (class "Default")
      (node (ref "LP$19") (pin "$1") (pinfunction "IN_$1") (pintype "bidirectional"))
      (node (ref "U$25") (pin "19") (pinfunction "19_19") (pintype "bidirectional"))
    )
    (net (code "20") (name "/DC$20") (class "Default")
      (node (ref "LP$20") (pin "$1") (pinfunction "IN_$1") (pintype "bidirectional"))
      (node (ref "U$25") (pin "20") (pinfunction "20_20") (pintype "bidirectional"))
    )
    (net (code "21") (name "/DC$21") (class "Default")
      (node (ref "LP$21") (pin "$1") (pinfunction "IN_$1") (pintype "bidirectional"))
      (node (ref "U$25") (pin "21") (pinfunction "21_21") (pintype "bidirectional"))
    )
    (net (code "22") (name "/DC$22") (class "Default")
      (node (ref "LP$22") (pin "$1") (pinfunction "IN_$1") (pintype "bidirectional"))
      (node (ref "U$25") (pin "22") (pinfunction "22_22") (pintype "bidirectional"))
    )
    (net (code "23") (name "/DC$23") (class "Default")
      (node (ref "LP$23") (pin "$1") (pinfunction "IN_$1") (pintype "bidirectional"))
      (node (ref "U$25") (pin "23") (pinfunction "23_23") (pintype "bidirectional"))
    )
    (net (code "24") (name "/DC$24") (class "Default")
      (node (ref "LP$24") (pin "$1") (pinfunction "IN_$1") (pintype "bidirectional"))
      (node (ref "U$25") (pin "24") (pinfunction "24_24") (pintype "bidirectional"))
    )
    (net (code "25") (name "/DC$25") (class "Default")
      (node (ref "LP$25") (pin "$1") (pinfunction "IN_$1") (pintype "bidirectional"))
      (node (ref "U$25") (pin "25") (pinfunction "25_25") (pintype "bidirectional"))
    )
    (net (code "26") (name "/DC$26") (class "Default")
      (node (ref "LP$26") (pin "$1") (pinfunction "IN_$1") (pintype "bidirectional"))
      (node (ref "U$25") (pin "26") (pinfunction "26_26") (pintype "bidirectional"))
    )
    (net (code "27") (name "/DC$27") (class "Default")
      (node (ref "LP$27") (pin "$1") (pinfunction "IN_$1") (pintype "bidirectional"))
      (node (ref "U$25") (pin "27") (pinfunction "27_27") (pintype "bidirectional"))
    )
    (net (code "28") (name "/DC$28") (class "Default")
      (node (ref "LP$28") (pin "$1") (pinfunction "IN_$1") (pintype "bidirectional"))
      (node (ref "U$25") (pin "28") (pinfunction "28_28") (pintype "bidirectional"))
    )
    (net (code "29") (name "/DC$29") (class "Default")
      (node (ref "LP$29") (pin "$1") (pinfunction "IN_$1") (pintype "bidirectional"))
      (node (ref "U$25") (pin "29") (pinfunction "29_29") (pintype "bidirectional"))
    )
    (net (code "30") (name "/DC$30") (class "Default")
      (node (ref "LP$30") (pin "$1") (pinfunction "IN_$1") (pintype "bidirectional"))
      (node (ref "U$25") (pin "30") (pinfunction "30_30") (pintype "bidirectional"))
    )
    (net (code "31") (name "/DC$31") (class "Default")
      (node (ref "LP$31") (pin "$1") (pinfunction "IN_$1") (pintype "bidirectional"))
      (node (ref "U$25") (pin "31") (pinfunction "31_31") (pintype "bidirectional"))
    )
    (net (code "32") (name "/DC$32") (class "Default")
      (node (ref "LP$32") (pin "$1") (pinfunction "IN_$1") (pintype "bidirectional"))
      (node (ref "U$25") (pin "32") (pinfunction "32_32") (pintype "bidirectional"))
    )
    (net (code "33") (name "/DC$33") (class "Default")
      (node (ref "LP$33") (pin "$1") (pinfunction "IN_$1") (pintype "bidirectional"))
      (node (ref "U$25") (pin "33") (pinfunction "33_33") (pintype "bidirectional"))
    )
    (net (code "34") (name "/DC$34") (class "Default")
      (node (ref "LP$34") (pin "$1") (pinfunction "IN_$1") (pintype "bidirectional"))
      (node (ref "U$25") (pin "34") (pinfunction "34_34") (pintype "bidirectional"))
    )
    (net (code "35") (name "/DC$35") (class "Default")
      (node (ref "LP$35") (pin "$1") (pinfunction "IN_$1") (pintype "bidirectional"))
      (node (ref "U$25") (pin "35") (pinfunction "35_35") (pintype "bidirectional"))
    )
    (net (code "36") (name "/DC$36") (class "Default")
      (node (ref "LP$36") (pin "$1") (pinfunction "IN_$1") (pintype "bidirectional"))
      (node (ref "U$25") (pin "36") (pinfunction "36_36") (pintype "bidirectional"))
    )
    (net (code "37") (name "/DC$37") (class "Default")
      (node (ref "LP$37") (pin "$1") (pinfunction "IN_$1") (pintype "bidirectional"))
      (node (ref "U$25") (pin "37") (pinfunction "37_37") (pintype "bidirectional"))
    )
    (net (code "38") (name "/DC$38") (class "Default")
      (node (ref "LP$38") (pin "$1") (pinfunction "IN_$1") (pintype "bidirectional"))
      (node (ref "U$25") (pin "38") (pinfunction "38_38") (pintype "bidirectional"))
    )
    (net (code "39") (name "/DC$39") (class "Default")
      (node (ref "LP$39") (pin "$1") (pinfunction "IN_$1") (pintype "bidirectional"))
      (node (ref "U$25") (pin "39") (pinfunction "39_39") (pintype "bidirectional"))
    )
    (net (code "40") (name "/DC$40") (class "Default")
      (node (ref "LP$40") (pin "$1") (pinfunction "IN_$1") (pintype "bidirectional"))
      (node (ref "U$25") (pin "40") (pinfunction "40_40") (pintype "bidirectional"))
    )
    (net (code "41") (name "/DC$41") (class "Default")
      (node (ref "LP$41") (pin "$1") (pinfunction "IN_$1") (pintype "bidirectional"))
      (node (ref "U$25") (pin "41") (pinfunction "41_41") (pintype "bidirectional"))
    )
    (net (code "42") (name "/DC$42") (class "Default")
      (node (ref "LP$42") (pin "$1") (pinfunction "IN_$1") (pintype "bidirectional"))
      (node (ref "U$25") (pin "42") (pinfunction "42_42") (pintype "bidirectional"))
    )
    (net (code "43") (name "/DC$43") (class "Default")
      (node (ref "LP$43") (pin "$1") (pinfunction "IN_$1") (pintype "bidirectional"))
      (node (ref "U$25") (pin "43") (pinfunction "43_43") (pintype "bidirectional"))
    )
    (net (code "44") (name "/DC$44") (class "Default")
      (node (ref "LP$44") (pin "$1") (pinfunction "IN_$1") (pintype "bidirectional"))
      (node (ref "U$25") (pin "44") (pinfunction "44_44") (pintype "bidirectional"))
    )
    (net (code "45") (name "/DC$45") (class "Default")
      (node (ref "LP$45") (pin "$1") (pinfunction "IN_$1") (pintype "bidirectional"))
      (node (ref "U$25") (pin "45") (pinfunction "45_45") (pintype "bidirectional"))
    )
    (net (code "46") (name "/DC$46") (class "Default")
      (node (ref "LP$46") (pin "$1") (pinfunction "IN_$1") (pintype "bidirectional"))
      (node (ref "U$25") (pin "46") (pinfunction "46_46") (pintype "bidirectional"))
    )
    (net (code "47") (name "/DC$47") (class "Default")
      (node (ref "LP$47") (pin "$1") (pinfunction "IN_$1") (pintype "bidirectional"))
      (node (ref "U$25") (pin "47") (pinfunction "47_47") (pintype "bidirectional"))
    )
    (net (code "48") (name "/DC$48") (class "Default")
      (node (ref "LP$48") (pin "$1") (pinfunction "IN_$1") (pintype "bidirectional"))
      (node (ref "U$25") (pin "48") (pinfunction "48_48") (pintype "bidirectional"))
    )
    (net (code "49") (name "/DCF$01") (class "Default")
      (node (ref "LP$1") (pin "$4") (pinfunction "OUT_$4") (pintype "bidirectional"))
      (node (ref "U$1") (pin "DC§1") (pinfunction "DC§01_DC§1") (pintype "bidirectional"))
      (node (ref "U$42") (pin "OUT") (pinfunction "2_OUT") (pintype "passive"))
      (node (ref "X1") (pin "P$1") (pinfunction "S_P$1") (pintype "passive"))
    )
    (net (code "50") (name "/DCF$02") (class "Default")
      (node (ref "LP$2") (pin "$4") (pinfunction "OUT_$4") (pintype "bidirectional"))
      (node (ref "U$1") (pin "DC§2") (pinfunction "DC§02_DC§2") (pintype "bidirectional"))
      (node (ref "U$43") (pin "OUT") (pinfunction "2_OUT") (pintype "passive"))
      (node (ref "X1") (pin "P$3") (pinfunction "S_P$3") (pintype "passive"))
    )
    (net (code "51") (name "/DCF$03") (class "Default")
      (node (ref "B$6") (pin "LF") (pinfunction "LF_LF") (pintype "bidirectional"))
      (node (ref "LP$3") (pin "$4") (pinfunction "OUT_$4") (pintype "bidirectional"))
      (node (ref "U$1") (pin "DC§3") (pinfunction "DC§03_DC§3") (pintype "bidirectional"))
      (node (ref "U$44") (pin "OUT") (pinfunction "2_OUT") (pintype "passive"))
      (node (ref "X1") (pin "P$5") (pinfunction "S_P$5") (pintype "passive"))
    )
    (net (code "52") (name "/DCF$04") (class "Default")
      (node (ref "B$11") (pin "LF") (pinfunction "LF_LF") (pintype "bidirectional"))
      (node (ref "LP$4") (pin "$4") (pinfunction "OUT_$4") (pintype "bidirectional"))
      (node (ref "U$1") (pin "DC§4") (pinfunction "DC§04_DC§4") (pintype "bidirectional"))
      (node (ref "U$45") (pin "OUT") (pinfunction "2_OUT") (pintype "passive"))
      (node (ref "X1") (pin "P$7") (pinfunction "S_P$7") (pintype "passive"))
    )
    (net (code "53") (name "/DCF$05") (class "Default")
      (node (ref "LP$5") (pin "$4") (pinfunction "OUT_$4") (pintype "bidirectional"))
      (node (ref "U$1") (pin "DC§5") (pinfunction "DC§05_DC§5") (pintype "bidirectional"))
      (node (ref "U$46") (pin "OUT") (pinfunction "2_OUT") (pintype "passive"))
      (node (ref "X1") (pin "P$9") (pinfunction "S_P$9") (pintype "passive"))
    )
    (net (code "54") (name "/DCF$06") (class "Default")
      (node (ref "LP$6") (pin "$4") (pinfunction "OUT_$4") (pintype "bidirectional"))
      (node (ref "U$1") (pin "DC§6") (pinfunction "DC§06_DC§6") (pintype "bidirectional"))
      (node (ref "U$47") (pin "OUT") (pinfunction "2_OUT") (pintype "passive"))
      (node (ref "X1") (pin "P$11") (pinfunction "S_P$11") (pintype "passive"))
    )
    (net (code "55") (name "/DCF$07") (class "Default")
      (node (ref "LP$7") (pin "$4") (pinfunction "OUT_$4") (pintype "bidirectional"))
      (node (ref "U$1") (pin "DC§7") (pinfunction "DC§07_DC§7") (pintype "bidirectional"))
      (node (ref "U$48") (pin "OUT") (pinfunction "2_OUT") (pintype "passive"))
      (node (ref "X1") (pin "P$13") (pinfunction "S_P$13") (pintype "passive"))
    )
    (net (code "56") (name "/DCF$08") (class "Default")
      (node (ref "B$12") (pin "LF") (pinfunction "LF_LF") (pintype "bidirectional"))
      (node (ref "LP$8") (pin "$4") (pinfunction "OUT_$4") (pintype "bidirectional"))
      (node (ref "U$1") (pin "DC§8") (pinfunction "DC§08_DC§8") (pintype "bidirectional"))
      (node (ref "U$49") (pin "OUT") (pinfunction "2_OUT") (pintype "passive"))
      (node (ref "X1") (pin "P$15") (pinfunction "S_P$15") (pintype "passive"))
    )
    (net (code "57") (name "/DCF$09") (class "Default")
      (node (ref "B$13") (pin "LF") (pinfunction "LF_LF") (pintype "bidirectional"))
      (node (ref "LP$9") (pin "$4") (pinfunction "OUT_$4") (pintype "bidirectional"))
      (node (ref "U$1") (pin "DC§9") (pinfunction "DC§09_DC§9") (pintype "bidirectional"))
      (node (ref "U$50") (pin "OUT") (pinfunction "2_OUT") (pintype "passive"))
      (node (ref "X1") (pin "P$17") (pinfunction "S_P$17") (pintype "passive"))
    )
    (net (code "58") (name "/DCF$10") (class "Default")
      (node (ref "LP$10") (pin "$4") (pinfunction "OUT_$4") (pintype "bidirectional"))
      (node (ref "U$1") (pin "DC§10") (pinfunction "DC§10_DC§10") (pintype "bidirectional"))
      (node (ref "U$51") (pin "OUT") (pinfunction "2_OUT") (pintype "passive"))
      (node (ref "X1") (pin "P$19") (pinfunction "S_P$19") (pintype "passive"))
    )
    (net (code "59") (name "/DCF$11") (class "Default")
      (node (ref "LP$11") (pin "$4") (pinfunction "OUT_$4") (pintype "bidirectional"))
      (node (ref "U$1") (pin "DC§11") (pinfunction "DC§11_DC§11") (pintype "bidirectional"))
      (node (ref "U$52") (pin "OUT") (pinfunction "2_OUT") (pintype "passive"))
      (node (ref "X1") (pin "P$21") (pinfunction "S_P$21") (pintype "passive"))
    )
    (net (code "60") (name "/DCF$12") (class "Default")
      (node (ref "LP$12") (pin "$4") (pinfunction "OUT_$4") (pintype "bidirectional"))
      (node (ref "U$1") (pin "DC§12") (pinfunction "DC§12_DC§12") (pintype "bidirectional"))
      (node (ref "U$53") (pin "OUT") (pinfunction "2_OUT") (pintype "passive"))
      (node (ref "X1") (pin "P$23") (pinfunction "S_P$23") (pintype "passive"))
    )
    (net (code "61") (name "/DCF$13") (class "Default")
      (node (ref "LP$13") (pin "$4") (pinfunction "OUT_$4") (pintype "bidirectional"))
      (node (ref "U$1") (pin "DC§13") (pinfunction "DC§13_DC§13") (pintype "bidirectional"))
      (node (ref "U$54") (pin "IN") (pinfunction "1_IN") (pintype "passive"))
      (node (ref "X1") (pin "P$25") (pinfunction "S_P$25") (pintype "passive"))
    )
    (net (code "62") (name "/DCF$14") (class "Default")
      (node (ref "LP$14") (pin "$4") (pinfunction "OUT_$4") (pintype "bidirectional"))
      (node (ref "U$1") (pin "DC§14") (pinfunction "DC§14_DC§14") (pintype "bidirectional"))
      (node (ref "U$55") (pin "IN") (pinfunction "1_IN") (pintype "passive"))
      (node (ref "X1") (pin "P$27") (pinfunction "S_P$27") (pintype "passive"))
    )
    (net (code "63") (name "/DCF$15") (class "Default")
      (node (ref "B$14") (pin "LF") (pinfunction "LF_LF") (pintype "bidirectional"))
      (node (ref "LP$15") (pin "$4") (pinfunction "OUT_$4") (pintype "bidirectional"))
      (node (ref "U$1") (pin "DC§15") (pinfunction "DC§15_DC§15") (pintype "bidirectional"))
      (node (ref "U$56") (pin "IN") (pinfunction "1_IN") (pintype "passive"))
      (node (ref "X1") (pin "P$29") (pinfunction "S_P$29") (pintype "passive"))
    )
    (net (code "64") (name "/DCF$16") (class "Default")
      (node (ref "B$15") (pin "LF") (pinfunction "LF_LF") (pintype "bidirectional"))
      (node (ref "LP$16") (pin "$4") (pinfunction "OUT_$4") (pintype "bidirectional"))
      (node (ref "U$1") (pin "DC§16") (pinfunction "DC§16_DC§16") (pintype "bidirectional"))
      (node (ref "U$57") (pin "IN") (pinfunction "1_IN") (pintype "passive"))
      (node (ref "X1") (pin "P$31") (pinfunction "S_P$31") (pintype "passive"))
    )
    (net (code "65") (name "/DCF$17") (class "Default")
      (node (ref "LP$17") (pin "$4") (pinfunction "OUT_$4") (pintype "bidirectional"))
      (node (ref "U$1") (pin "DC§17") (pinfunction "DC§17_DC§17") (pintype "bidirectional"))
      (node (ref "U$58") (pin "IN") (pinfunction "1_IN") (pintype "passive"))
      (node (ref "X1") (pin "P$33") (pinfunction "S_P$33") (pintype "passive"))
    )
    (net (code "66") (name "/DCF$18") (class "Default")
      (node (ref "LP$18") (pin "$4") (pinfunction "OUT_$4") (pintype "bidirectional"))
      (node (ref "U$1") (pin "DC§18") (pinfunction "DC§18_DC§18") (pintype "bidirectional"))
      (node (ref "U$59") (pin "IN") (pinfunction "1_IN") (pintype "passive"))
      (node (ref "X1") (pin "P$35") (pinfunction "S_P$35") (pintype "passive"))
    )
    (net (code "67") (name "/DCF$19") (class "Default")
      (node (ref "LP$19") (pin "$4") (pinfunction "OUT_$4") (pintype "bidirectional"))
      (node (ref "U$1") (pin "DC§19") (pinfunction "DC§019_DC§19") (pintype "bidirectional"))
      (node (ref "U$60") (pin "IN") (pinfunction "1_IN") (pintype "passive"))
      (node (ref "X1") (pin "P$37") (pinfunction "S_P$37") (pintype "passive"))
    )
    (net (code "68") (name "/DCF$20") (class "Default")
      (node (ref "B$16") (pin "LF") (pinfunction "LF_LF") (pintype "bidirectional"))
      (node (ref "LP$20") (pin "$4") (pinfunction "OUT_$4") (pintype "bidirectional"))
      (node (ref "U$1") (pin "DC§20") (pinfunction "DC§20_DC§20") (pintype "bidirectional"))
      (node (ref "U$61") (pin "IN") (pinfunction "1_IN") (pintype "passive"))
      (node (ref "X1") (pin "P$39") (pinfunction "S_P$39") (pintype "passive"))
    )
    (net (code "69") (name "/DCF$21") (class "Default")
      (node (ref "B$17") (pin "LF") (pinfunction "LF_LF") (pintype "bidirectional"))
      (node (ref "LP$21") (pin "$4") (pinfunction "OUT_$4") (pintype "bidirectional"))
      (node (ref "U$1") (pin "DC§21") (pinfunction "DC§21_DC§21") (pintype "bidirectional"))
      (node (ref "U$62") (pin "IN") (pinfunction "1_IN") (pintype "passive"))
      (node (ref "X1") (pin "P$41") (pinfunction "S_P$41") (pintype "passive"))
    )
    (net (code "70") (name "/DCF$22") (class "Default")
      (node (ref "LP$22") (pin "$4") (pinfunction "OUT_$4") (pintype "bidirectional"))
      (node (ref "U$1") (pin "DC§22") (pinfunction "DC§22_DC§22") (pintype "bidirectional"))
      (node (ref "U$63") (pin "IN") (pinfunction "1_IN") (pintype "passive"))
      (node (ref "X1") (pin "P$43") (pinfunction "S_P$43") (pintype "passive"))
    )
    (net (code "71") (name "/DCF$23") (class "Default")
      (node (ref "LP$23") (pin "$4") (pinfunction "OUT_$4") (pintype "bidirectional"))
      (node (ref "U$1") (pin "DC§23") (pinfunction "DC§23_DC§23") (pintype "bidirectional"))
      (node (ref "U$64") (pin "IN") (pinfunction "1_IN") (pintype "passive"))
      (node (ref "X1") (pin "P$45") (pinfunction "S_P$45") (pintype "passive"))
    )
    (net (code "72") (name "/DCF$24") (class "Default")
      (node (ref "B$5") (pin "LF") (pinfunction "LF_LF") (pintype "bidirectional"))
      (node (ref "LP$24") (pin "$4") (pinfunction "OUT_$4") (pintype "bidirectional"))
      (node (ref "U$1") (pin "DC§24") (pinfunction "DC§24_DC§24") (pintype "bidirectional"))
      (node (ref "U$65") (pin "IN") (pinfunction "1_IN") (pintype "passive"))
      (node (ref "X1") (pin "P$47") (pinfunction "S_P$47") (pintype "passive"))
    )
    (net (code "73") (name "/DCF$25") (class "Default")
      (node (ref "LP$25") (pin "$4") (pinfunction "OUT_$4") (pintype "bidirectional"))
      (node (ref "U$1") (pin "DC§25") (pinfunction "DC§025_DC§25") (pintype "bidirectional"))
      (node (ref "U$31") (pin "OUT1") (pinfunction "2_OUT1") (pintype "passive"))
      (node (ref "U$32") (pin "OUT") (pinfunction "2_OUT") (pintype "passive"))
      (node (ref "U$66") (pin "IN") (pinfunction "1_IN") (pintype "passive"))
      (node (ref "X1") (pin "P$48") (pinfunction "S_P$48") (pintype "passive"))
    )
    (net (code "74") (name "/DCF$26") (class "Default")
      (node (ref "LP$26") (pin "$4") (pinfunction "OUT_$4") (pintype "bidirectional"))
      (node (ref "U$1") (pin "DC§26") (pinfunction "DC§026_DC§26") (pintype "bidirectional"))
      (node (ref "U$2") (pin "OUT") (pinfunction "1_OUT") (pintype "passive"))
      (node (ref "U$3") (pin "IN") (pinfunction "1_IN") (pintype "passive"))
      (node (ref "U$67") (pin "IN") (pinfunction "1_IN") (pintype "passive"))
      (node (ref "X1") (pin "P$46") (pinfunction "S_P$46") (pintype "passive"))
    )
    (net (code "75") (name "/DCF$27") (class "Default")
      (node (ref "B$10") (pin "LF") (pinfunction "LF_LF") (pintype "bidirectional"))
      (node (ref "LP$27") (pin "$4") (pinfunction "OUT_$4") (pintype "bidirectional"))
      (node (ref "U$1") (pin "DC§27") (pinfunction "DC§027_DC§27") (pintype "bidirectional"))
      (node (ref "U$68") (pin "IN") (pinfunction "1_IN") (pintype "passive"))
      (node (ref "X1") (pin "P$44") (pinfunction "S_P$44") (pintype "passive"))
    )
    (net (code "76") (name "/DCF$28") (class "Default")
      (node (ref "B$18") (pin "LF") (pinfunction "LF_LF") (pintype "bidirectional"))
      (node (ref "LP$28") (pin "$4") (pinfunction "OUT_$4") (pintype "bidirectional"))
      (node (ref "U$1") (pin "DC§28") (pinfunction "DC§028_DC§28") (pintype "bidirectional"))
      (node (ref "U$69") (pin "IN") (pinfunction "1_IN") (pintype "passive"))
      (node (ref "X1") (pin "P$42") (pinfunction "S_P$42") (pintype "passive"))
    )
    (net (code "77") (name "/DCF$29") (class "Default")
      (node (ref "LP$29") (pin "$4") (pinfunction "OUT_$4") (pintype "bidirectional"))
      (node (ref "U$1") (pin "DC§29") (pinfunction "DC§029_DC§29") (pintype "bidirectional"))
      (node (ref "U$70") (pin "IN") (pinfunction "1_IN") (pintype "passive"))
      (node (ref "X1") (pin "P$40") (pinfunction "S_P$40") (pintype "passive"))
    )
    (net (code "78") (name "/DCF$30") (class "Default")
      (node (ref "LP$30") (pin "$4") (pinfunction "OUT_$4") (pintype "bidirectional"))
      (node (ref "U$1") (pin "DC§30") (pinfunction "DC§030_DC§30") (pintype "bidirectional"))
      (node (ref "U$71") (pin "IN") (pinfunction "1_IN") (pintype "passive"))
      (node (ref "X1") (pin "P$38") (pinfunction "S_P$38") (pintype "passive"))
    )
    (net (code "79") (name "/DCF$31") (class "Default")
      (node (ref "LP$31") (pin "$4") (pinfunction "OUT_$4") (pintype "bidirectional"))
      (node (ref "U$1") (pin "DC§31") (pinfunction "DC§031_DC§31") (pintype "bidirectional"))
      (node (ref "U$72") (pin "IN") (pinfunction "1_IN") (pintype "passive"))
      (node (ref "X1") (pin "P$36") (pinfunction "S_P$36") (pintype "passive"))
    )
    (net (code "80") (name "/DCF$32") (class "Default")
      (node (ref "B$19") (pin "LF") (pinfunction "LF_LF") (pintype "bidirectional"))
      (node (ref "LP$32") (pin "$4") (pinfunction "OUT_$4") (pintype "bidirectional"))
      (node (ref "U$1") (pin "DC§32") (pinfunction "DC§032_DC§32") (pintype "bidirectional"))
      (node (ref "U$73") (pin "IN") (pinfunction "1_IN") (pintype "passive"))
      (node (ref "X1") (pin "P$34") (pinfunction "S_P$34") (pintype "passive"))
    )
    (net (code "81") (name "/DCF$33") (class "Default")
      (node (ref "B$20") (pin "LF") (pinfunction "LF_LF") (pintype "bidirectional"))
      (node (ref "LP$33") (pin "$4") (pinfunction "OUT_$4") (pintype "bidirectional"))
      (node (ref "U$1") (pin "DC§33") (pinfunction "DC§033_DC§33") (pintype "bidirectional"))
      (node (ref "U$74") (pin "IN") (pinfunction "1_IN") (pintype "passive"))
      (node (ref "X1") (pin "P$32") (pinfunction "S_P$32") (pintype "passive"))
    )
    (net (code "82") (name "/DCF$34") (class "Default")
      (node (ref "LP$34") (pin "$4") (pinfunction "OUT_$4") (pintype "bidirectional"))
      (node (ref "U$1") (pin "DC§34") (pinfunction "DC§034_DC§34") (pintype "bidirectional"))
      (node (ref "U$75") (pin "IN") (pinfunction "1_IN") (pintype "passive"))
      (node (ref "X1") (pin "P$30") (pinfunction "S_P$30") (pintype "passive"))
    )
    (net (code "83") (name "/DCF$35") (class "Default")
      (node (ref "LP$35") (pin "$4") (pinfunction "OUT_$4") (pintype "bidirectional"))
      (node (ref "U$1") (pin "DC§35") (pinfunction "DC§035_DC§35") (pintype "bidirectional"))
      (node (ref "U$76") (pin "IN") (pinfunction "1_IN") (pintype "passive"))
      (node (ref "X1") (pin "P$28") (pinfunction "S_P$28") (pintype "passive"))
    )
    (net (code "84") (name "/DCF$36") (class "Default")
      (node (ref "LP$36") (pin "$4") (pinfunction "OUT_$4") (pintype "bidirectional"))
      (node (ref "U$1") (pin "DC§36") (pinfunction "DC§036_DC§36") (pintype "bidirectional"))
      (node (ref "U$77") (pin "IN") (pinfunction "1_IN") (pintype "passive"))
      (node (ref "X1") (pin "P$26") (pinfunction "S_P$26") (pintype "passive"))
    )
    (net (code "85") (name "/DCF$37") (class "Default")
      (node (ref "LP$37") (pin "$4") (pinfunction "OUT_$4") (pintype "bidirectional"))
      (node (ref "U$1") (pin "DC§37") (pinfunction "DC§037_DC§37") (pintype "bidirectional"))
      (node (ref "U$78") (pin "IN") (pinfunction "1_IN") (pintype "passive"))
      (node (ref "X1") (pin "P$24") (pinfunction "S_P$24") (pintype "passive"))
    )
    (net (code "86") (name "/DCF$38") (class "Default")
      (node (ref "LP$38") (pin "$4") (pinfunction "OUT_$4") (pintype "bidirectional"))
      (node (ref "U$1") (pin "DC§38") (pinfunction "DC§038_DC§38") (pintype "bidirectional"))
      (node (ref "U$79") (pin "IN") (pinfunction "1_IN") (pintype "passive"))
      (node (ref "X1") (pin "P$22") (pinfunction "S_P$22") (pintype "passive"))
    )
    (net (code "87") (name "/DCF$39") (class "Default")
      (node (ref "B$21") (pin "LF") (pinfunction "LF_LF") (pintype "bidirectional"))
      (node (ref "LP$39") (pin "$4") (pinfunction "OUT_$4") (pintype "bidirectional"))
      (node (ref "U$1") (pin "DC§39") (pinfunction "DC§039_DC§39") (pintype "bidirectional"))
      (node (ref "U$80") (pin "IN") (pinfunction "1_IN") (pintype "passive"))
      (node (ref "X1") (pin "P$20") (pinfunction "S_P$20") (pintype "passive"))
    )
    (net (code "88") (name "/DCF$40") (class "Default")
      (node (ref "B$22") (pin "LF") (pinfunction "LF_LF") (pintype "bidirectional"))
      (node (ref "LP$40") (pin "$4") (pinfunction "OUT_$4") (pintype "bidirectional"))
      (node (ref "U$1") (pin "DC§40") (pinfunction "DC§040_DC§40") (pintype "bidirectional"))
      (node (ref "U$81") (pin "IN") (pinfunction "1_IN") (pintype "passive"))
      (node (ref "X1") (pin "P$18") (pinfunction "S_P$18") (pintype "passive"))
    )
    (net (code "89") (name "/DCF$41") (class "Default")
      (node (ref "LP$41") (pin "$4") (pinfunction "OUT_$4") (pintype "bidirectional"))
      (node (ref "U$1") (pin "DC§41") (pinfunction "DC§041_DC§41") (pintype "bidirectional"))
      (node (ref "U$82") (pin "IN") (pinfunction "1_IN") (pintype "passive"))
      (node (ref "X1") (pin "P$16") (pinfunction "S_P$16") (pintype "passive"))
    )
    (net (code "90") (name "/DCF$42") (class "Default")
      (node (ref "LP$42") (pin "$4") (pinfunction "OUT_$4") (pintype "bidirectional"))
      (node (ref "U$1") (pin "DC§42") (pinfunction "DC§042_DC§42") (pintype "bidirectional"))
      (node (ref "U$83") (pin "IN") (pinfunction "1_IN") (pintype "passive"))
      (node (ref "X1") (pin "P$14") (pinfunction "S_P$14") (pintype "passive"))
    )
    (net (code "91") (name "/DCF$43") (class "Default")
      (node (ref "LP$43") (pin "$4") (pinfunction "OUT_$4") (pintype "bidirectional"))
      (node (ref "U$1") (pin "DC§43") (pinfunction "DC§043_DC§43") (pintype "bidirectional"))
      (node (ref "U$84") (pin "IN") (pinfunction "1_IN") (pintype "passive"))
      (node (ref "X1") (pin "P$12") (pinfunction "S_P$12") (pintype "passive"))
    )
    (net (code "92") (name "/DCF$44") (class "Default")
      (node (ref "B$23") (pin "LF") (pinfunction "LF_LF") (pintype "bidirectional"))
      (node (ref "LP$44") (pin "$4") (pinfunction "OUT_$4") (pintype "bidirectional"))
      (node (ref "U$1") (pin "DC§44") (pinfunction "DC§044_DC§44") (pintype "bidirectional"))
      (node (ref "U$85") (pin "IN") (pinfunction "1_IN") (pintype "passive"))
      (node (ref "X1") (pin "P$10") (pinfunction "S_P$10") (pintype "passive"))
    )
    (net (code "93") (name "/DCF$45") (class "Default")
      (node (ref "B$24") (pin "LF") (pinfunction "LF_LF") (pintype "bidirectional"))
      (node (ref "LP$45") (pin "$4") (pinfunction "OUT_$4") (pintype "bidirectional"))
      (node (ref "U$1") (pin "DC§45") (pinfunction "DC§045_DC§45") (pintype "bidirectional"))
      (node (ref "U$86") (pin "IN") (pinfunction "1_IN") (pintype "passive"))
      (node (ref "X1") (pin "P$8") (pinfunction "S_P$8") (pintype "passive"))
    )
    (net (code "94") (name "/DCF$46") (class "Default")
      (node (ref "LP$46") (pin "$4") (pinfunction "OUT_$4") (pintype "bidirectional"))
      (node (ref "U$1") (pin "DC§46") (pinfunction "DC§046_DC§46") (pintype "bidirectional"))
      (node (ref "U$87") (pin "IN") (pinfunction "1_IN") (pintype "passive"))
      (node (ref "X1") (pin "P$6") (pinfunction "S_P$6") (pintype "passive"))
    )
    (net (code "95") (name "/DCF$47") (class "Default")
      (node (ref "LP$47") (pin "$4") (pinfunction "OUT_$4") (pintype "bidirectional"))
      (node (ref "U$1") (pin "DC§47") (pinfunction "DC§047_DC§47") (pintype "bidirectional"))
      (node (ref "U$88") (pin "IN") (pinfunction "1_IN") (pintype "passive"))
      (node (ref "X1") (pin "P$4") (pinfunction "S_P$4") (pintype "passive"))
    )
    (net (code "96") (name "/DCF$48") (class "Default")
      (node (ref "LP$48") (pin "$4") (pinfunction "OUT_$4") (pintype "bidirectional"))
      (node (ref "U$1") (pin "DC§48") (pinfunction "DC§048_DC§48") (pintype "bidirectional"))
      (node (ref "U$89") (pin "IN") (pinfunction "1_IN") (pintype "passive"))
      (node (ref "X1") (pin "P$2") (pinfunction "S_P$2") (pintype "passive"))
    )
    (net (code "97") (name "/RF$R4") (class "Default")
      (node (ref "L$6") (pin "OUT") (pinfunction "OUT_OUT") (pintype "passive"))
      (node (ref "U$1") (pin "RF$24_R4") (pinfunction "RF$24_R4_RF$24_R4") (pintype "bidirectional"))
      (node (ref "U$31") (pin "OUT") (pinfunction "1_OUT") (pintype "passive"))
    )
    (net (code "98") (name "GND") (class "Default")
      (node (ref "LP$1") (pin "$6") (pinfunction "GND_$6") (pintype "bidirectional"))
      (node (ref "LP$10") (pin "$6") (pinfunction "GND_$6") (pintype "bidirectional"))
      (node (ref "LP$11") (pin "$6") (pinfunction "GND_$6") (pintype "bidirectional"))
      (node (ref "LP$12") (pin "$6") (pinfunction "GND_$6") (pintype "bidirectional"))
      (node (ref "LP$13") (pin "$6") (pinfunction "GND_$6") (pintype "bidirectional"))
      (node (ref "LP$14") (pin "$6") (pinfunction "GND_$6") (pintype "bidirectional"))
      (node (ref "LP$15") (pin "$6") (pinfunction "GND_$6") (pintype "bidirectional"))
      (node (ref "LP$16") (pin "$6") (pinfunction "GND_$6") (pintype "bidirectional"))
      (node (ref "LP$17") (pin "$6") (pinfunction "GND_$6") (pintype "bidirectional"))
      (node (ref "LP$18") (pin "$6") (pinfunction "GND_$6") (pintype "bidirectional"))
      (node (ref "LP$19") (pin "$6") (pinfunction "GND_$6") (pintype "bidirectional"))
      (node (ref "LP$2") (pin "$6") (pinfunction "GND_$6") (pintype "bidirectional"))
      (node (ref "LP$20") (pin "$6") (pinfunction "GND_$6") (pintype "bidirectional"))
      (node (ref "LP$21") (pin "$6") (pinfunction "GND_$6") (pintype "bidirectional"))
      (node (ref "LP$22") (pin "$6") (pinfunction "GND_$6") (pintype "bidirectional"))
      (node (ref "LP$23") (pin "$6") (pinfunction "GND_$6") (pintype "bidirectional"))
      (node (ref "LP$24") (pin "$6") (pinfunction "GND_$6") (pintype "bidirectional"))
      (node (ref "LP$25") (pin "$6") (pinfunction "GND_$6") (pintype "bidirectional"))
      (node (ref "LP$26") (pin "$6") (pinfunction "GND_$6") (pintype "bidirectional"))
      (node (ref "LP$27") (pin "$6") (pinfunction "GND_$6") (pintype "bidirectional"))
      (node (ref "LP$28") (pin "$6") (pinfunction "GND_$6") (pintype "bidirectional"))
      (node (ref "LP$29") (pin "$6") (pinfunction "GND_$6") (pintype "bidirectional"))
      (node (ref "LP$3") (pin "$6") (pinfunction "GND_$6") (pintype "bidirectional"))
      (node (ref "LP$30") (pin "$6") (pinfunction "GND_$6") (pintype "bidirectional"))
      (node (ref "LP$31") (pin "$6") (pinfunction "GND_$6") (pintype "bidirectional"))
      (node (ref "LP$32") (pin "$6") (pinfunction "GND_$6") (pintype "bidirectional"))
      (node (ref "LP$33") (pin "$6") (pinfunction "GND_$6") (pintype "bidirectional"))
      (node (ref "LP$34") (pin "$6") (pinfunction "GND_$6") (pintype "bidirectional"))
      (node (ref "LP$35") (pin "$6") (pinfunction "GND_$6") (pintype "bidirectional"))
      (node (ref "LP$36") (pin "$6") (pinfunction "GND_$6") (pintype "bidirectional"))
      (node (ref "LP$37") (pin "$6") (pinfunction "GND_$6") (pintype "bidirectional"))
      (node (ref "LP$38") (pin "$6") (pinfunction "GND_$6") (pintype "bidirectional"))
      (node (ref "LP$39") (pin "$6") (pinfunction "GND_$6") (pintype "bidirectional"))
      (node (ref "LP$4") (pin "$6") (pinfunction "GND_$6") (pintype "bidirectional"))
      (node (ref "LP$40") (pin "$6") (pinfunction "GND_$6") (pintype "bidirectional"))
      (node (ref "LP$41") (pin "$6") (pinfunction "GND_$6") (pintype "bidirectional"))
      (node (ref "LP$42") (pin "$6") (pinfunction "GND_$6") (pintype "bidirectional"))
      (node (ref "LP$43") (pin "$6") (pinfunction "GND_$6") (pintype "bidirectional"))
      (node (ref "LP$44") (pin "$6") (pinfunction "GND_$6") (pintype "bidirectional"))
      (node (ref "LP$45") (pin "$6") (pinfunction "GND_$6") (pintype "bidirectional"))
      (node (ref "LP$46") (pin "$6") (pinfunction "GND_$6") (pintype "bidirectional"))
      (node (ref "LP$47") (pin "$6") (pinfunction "GND_$6") (pintype "bidirectional"))
      (node (ref "LP$48") (pin "$6") (pinfunction "GND_$6") (pintype "bidirectional"))
      (node (ref "LP$5") (pin "$6") (pinfunction "GND_$6") (pintype "bidirectional"))
      (node (ref "LP$6") (pin "$6") (pinfunction "GND_$6") (pintype "bidirectional"))
      (node (ref "LP$7") (pin "$6") (pinfunction "GND_$6") (pintype "bidirectional"))
      (node (ref "LP$8") (pin "$6") (pinfunction "GND_$6") (pintype "bidirectional"))
      (node (ref "LP$9") (pin "$6") (pinfunction "GND_$6") (pintype "bidirectional"))
      (node (ref "S$1") (pin "2@1") (pinfunction "GND_2@1") (pintype "passive"))
      (node (ref "S$1") (pin "2@2") (pinfunction "GND_2@2") (pintype "passive"))
      (node (ref "S$10") (pin "2@1") (pinfunction "GND_2@1") (pintype "passive"))
      (node (ref "S$10") (pin "2@2") (pinfunction "GND_2@2") (pintype "passive"))
      (node (ref "S$11") (pin "2@1") (pinfunction "GND_2@1") (pintype "passive"))
      (node (ref "S$11") (pin "2@2") (pinfunction "GND_2@2") (pintype "passive"))
      (node (ref "S$12") (pin "2@1") (pinfunction "GND_2@1") (pintype "passive"))
      (node (ref "S$12") (pin "2@2") (pinfunction "GND_2@2") (pintype "passive"))
      (node (ref "S$13") (pin "2@1") (pinfunction "GND_2@1") (pintype "passive"))
      (node (ref "S$13") (pin "2@2") (pinfunction "GND_2@2") (pintype "passive"))
      (node (ref "S$14") (pin "2@1") (pinfunction "GND_2@1") (pintype "passive"))
      (node (ref "S$14") (pin "2@2") (pinfunction "GND_2@2") (pintype "passive"))
      (node (ref "S$15") (pin "2@1") (pinfunction "GND_2@1") (pintype "passive"))
      (node (ref "S$15") (pin "2@2") (pinfunction "GND_2@2") (pintype "passive"))
      (node (ref "S$16") (pin "2@1") (pinfunction "GND_2@1") (pintype "passive"))
      (node (ref "S$16") (pin "2@2") (pinfunction "GND_2@2") (pintype "passive"))
      (node (ref "S$17") (pin "2@1") (pinfunction "GND_2@1") (pintype "passive"))
      (node (ref "S$17") (pin "2@2") (pinfunction "GND_2@2") (pintype "passive"))
      (node (ref "S$2") (pin "2@1") (pinfunction "GND_2@1") (pintype "passive"))
      (node (ref "S$2") (pin "2@2") (pinfunction "GND_2@2") (pintype "passive"))
      (node (ref "S$3") (pin "2@1") (pinfunction "GND_2@1") (pintype "passive"))
      (node (ref "S$3") (pin "2@2") (pinfunction "GND_2@2") (pintype "passive"))
      (node (ref "S$4") (pin "2@1") (pinfunction "GND_2@1") (pintype "passive"))
      (node (ref "S$4") (pin "2@2") (pinfunction "GND_2@2") (pintype "passive"))
      (node (ref "S$5") (pin "GND") (pinfunction "GND_GND") (pintype "passive"))
      (node (ref "S$5") (pin "GND@1") (pinfunction "GND_GND@1") (pintype "passive"))
      (node (ref "S$6") (pin "2@1") (pinfunction "GND_2@1") (pintype "passive"))
      (node (ref "S$6") (pin "2@2") (pinfunction "GND_2@2") (pintype "passive"))
      (node (ref "S$7") (pin "2@1") (pinfunction "GND_2@1") (pintype "passive"))
      (node (ref "S$7") (pin "2@2") (pinfunction "GND_2@2") (pintype "passive"))
      (node (ref "S$8") (pin "2@1") (pinfunction "GND_2@1") (pintype "passive"))
      (node (ref "S$8") (pin "2@2") (pinfunction "GND_2@2") (pintype "passive"))
      (node (ref "S$9") (pin "2@1") (pinfunction "GND_2@1") (pintype "passive"))
      (node (ref "S$9") (pin "2@2") (pinfunction "GND_2@2") (pintype "passive"))
      (node (ref "U$25") (pin "49") (pinfunction "49_49") (pintype "bidirectional"))
      (node (ref "U$25") (pin "50") (pinfunction "50_50") (pintype "bidirectional"))
      (node (ref "U$25") (pin "51") (pinfunction "51_51") (pintype "bidirectional"))
      (node (ref "U$3") (pin "OUT") (pinfunction "2_OUT") (pintype "passive"))
      (node (ref "U$32") (pin "IN") (pinfunction "1_IN") (pintype "passive"))
      (node (ref "U$42") (pin "IN") (pinfunction "1_IN") (pintype "passive"))
      (node (ref "U$43") (pin "IN") (pinfunction "1_IN") (pintype "passive"))
      (node (ref "U$44") (pin "IN") (pinfunction "1_IN") (pintype "passive"))
      (node (ref "U$45") (pin "IN") (pinfunction "1_IN") (pintype "passive"))
      (node (ref "U$46") (pin "IN") (pinfunction "1_IN") (pintype "passive"))
      (node (ref "U$47") (pin "IN") (pinfunction "1_IN") (pintype "passive"))
      (node (ref "U$48") (pin "IN") (pinfunction "1_IN") (pintype "passive"))
      (node (ref "U$49") (pin "IN") (pinfunction "1_IN") (pintype "passive"))
      (node (ref "U$50") (pin "IN") (pinfunction "1_IN") (pintype "passive"))
      (node (ref "U$51") (pin "IN") (pinfunction "1_IN") (pintype "passive"))
      (node (ref "U$52") (pin "IN") (pinfunction "1_IN") (pintype "passive"))
      (node (ref "U$53") (pin "IN") (pinfunction "1_IN") (pintype "passive"))
      (node (ref "U$54") (pin "OUT") (pinfunction "2_OUT") (pintype "passive"))
      (node (ref "U$55") (pin "OUT") (pinfunction "2_OUT") (pintype "passive"))
      (node (ref "U$56") (pin "OUT") (pinfunction "2_OUT") (pintype "passive"))
      (node (ref "U$57") (pin "OUT") (pinfunction "2_OUT") (pintype "passive"))
      (node (ref "U$58") (pin "OUT") (pinfunction "2_OUT") (pintype "passive"))
      (node (ref "U$59") (pin "OUT") (pinfunction "2_OUT") (pintype "passive"))
      (node (ref "U$60") (pin "OUT") (pinfunction "2_OUT") (pintype "passive"))
      (node (ref "U$61") (pin "OUT") (pinfunction "2_OUT") (pintype "passive"))
      (node (ref "U$62") (pin "OUT") (pinfunction "2_OUT") (pintype "passive"))
      (node (ref "U$63") (pin "OUT") (pinfunction "2_OUT") (pintype "passive"))
      (node (ref "U$64") (pin "OUT") (pinfunction "2_OUT") (pintype "passive"))
      (node (ref "U$65") (pin "OUT") (pinfunction "2_OUT") (pintype "passive"))
      (node (ref "U$66") (pin "OUT") (pinfunction "2_OUT") (pintype "passive"))
      (node (ref "U$67") (pin "OUT") (pinfunction "2_OUT") (pintype "passive"))
      (node (ref "U$68") (pin "OUT") (pinfunction "2_OUT") (pintype "passive"))
      (node (ref "U$69") (pin "OUT") (pinfunction "2_OUT") (pintype "passive"))
      (node (ref "U$70") (pin "OUT") (pinfunction "2_OUT") (pintype "passive"))
      (node (ref "U$71") (pin "OUT") (pinfunction "2_OUT") (pintype "passive"))
      (node (ref "U$72") (pin "OUT") (pinfunction "2_OUT") (pintype "passive"))
      (node (ref "U$73") (pin "OUT") (pinfunction "2_OUT") (pintype "passive"))
      (node (ref "U$74") (pin "OUT") (pinfunction "2_OUT") (pintype "passive"))
      (node (ref "U$75") (pin "OUT") (pinfunction "2_OUT") (pintype "passive"))
      (node (ref "U$76") (pin "OUT") (pinfunction "2_OUT") (pintype "passive"))
      (node (ref "U$77") (pin "OUT") (pinfunction "2_OUT") (pintype "passive"))
      (node (ref "U$78") (pin "OUT") (pinfunction "2_OUT") (pintype "passive"))
      (node (ref "U$79") (pin "OUT") (pinfunction "2_OUT") (pintype "passive"))
      (node (ref "U$80") (pin "OUT") (pinfunction "2_OUT") (pintype "passive"))
      (node (ref "U$81") (pin "OUT") (pinfunction "2_OUT") (pintype "passive"))
      (node (ref "U$82") (pin "OUT") (pinfunction "2_OUT") (pintype "passive"))
      (node (ref "U$83") (pin "OUT") (pinfunction "2_OUT") (pintype "passive"))
      (node (ref "U$84") (pin "OUT") (pinfunction "2_OUT") (pintype "passive"))
      (node (ref "U$85") (pin "OUT") (pinfunction "2_OUT") (pintype "passive"))
      (node (ref "U$86") (pin "OUT") (pinfunction "2_OUT") (pintype "passive"))
      (node (ref "U$87") (pin "OUT") (pinfunction "2_OUT") (pintype "passive"))
      (node (ref "U$88") (pin "OUT") (pinfunction "2_OUT") (pintype "passive"))
      (node (ref "U$89") (pin "OUT") (pinfunction "2_OUT") (pintype "passive"))
      (node (ref "X1") (pin "P$49") (pinfunction "S_P$49") (pintype "passive"))
      (node (ref "X1") (pin "P$50") (pinfunction "S_P$50") (pintype "passive"))
    )
    (net (code "99") (name "Net-(B$5-PadHF)") (class "Default")
      (node (ref "B$5") (pin "HF") (pinfunction "HF_HF") (pintype "bidirectional"))
      (node (ref "S$5") (pin "1") (pinfunction "1_1") (pintype "passive"))
    )
    (net (code "100") (name "Net-(B$6-PadHF)") (class "Default")
      (node (ref "B$6") (pin "HF") (pinfunction "HF_HF") (pintype "bidirectional"))
      (node (ref "S$1") (pin "1") (pinfunction "1_1") (pintype "passive"))
    )
    (net (code "101") (name "Net-(B$6-PadOUT)") (class "Default")
      (node (ref "B$6") (pin "OUT") (pinfunction "OUT_OUT") (pintype "bidirectional"))
      (node (ref "U$1") (pin "RF$03_G1") (pinfunction "RF$03_G1_RF$03_G1") (pintype "bidirectional"))
    )
    (net (code "102") (name "Net-(B$10-PadHF)") (class "Default")
      (node (ref "B$10") (pin "HF") (pinfunction "HF_HF") (pintype "bidirectional"))
      (node (ref "S$2") (pin "1") (pinfunction "1_1") (pintype "passive"))
    )
    (net (code "103") (name "Net-(B$10-PadOUT)") (class "Default")
      (node (ref "B$10") (pin "OUT") (pinfunction "OUT_OUT") (pintype "bidirectional"))
      (node (ref "U$1") (pin "RF$27_G9") (pinfunction "RF$27_G9_RF$27_G9") (pintype "bidirectional"))
    )
    (net (code "104") (name "Net-(B$11-PadHF)") (class "Default")
      (node (ref "B$11") (pin "HF") (pinfunction "HF_HF") (pintype "bidirectional"))
      (node (ref "S$8") (pin "1") (pinfunction "1_1") (pintype "passive"))
    )
    (net (code "105") (name "Net-(B$11-PadOUT)") (class "Default")
      (node (ref "B$11") (pin "OUT") (pinfunction "OUT_OUT") (pintype "bidirectional"))
      (node (ref "U$1") (pin "RF$04_G2") (pinfunction "RF$04_G2_RF$04_G2") (pintype "bidirectional"))
    )
    (net (code "106") (name "Net-(B$12-PadHF)") (class "Default")
      (node (ref "B$12") (pin "HF") (pinfunction "HF_HF") (pintype "bidirectional"))
      (node (ref "S$9") (pin "1") (pinfunction "1_1") (pintype "passive"))
    )
    (net (code "107") (name "Net-(B$12-PadOUT)") (class "Default")
      (node (ref "B$12") (pin "OUT") (pinfunction "OUT_OUT") (pintype "bidirectional"))
      (node (ref "U$1") (pin "RF$08_G3") (pinfunction "RF$08_G3_RF$08_G3") (pintype "bidirectional"))
    )
    (net (code "108") (name "Net-(B$13-PadHF)") (class "Default")
      (node (ref "B$13") (pin "HF") (pinfunction "HF_HF") (pintype "bidirectional"))
      (node (ref "S$10") (pin "1") (pinfunction "1_1") (pintype "passive"))
    )
    (net (code "109") (name "Net-(B$13-PadOUT)") (class "Default")
      (node (ref "B$13") (pin "OUT") (pinfunction "OUT_OUT") (pintype "bidirectional"))
      (node (ref "U$1") (pin "RF$09_G4") (pinfunction "RF$09_G4_RF$09_G4") (pintype "bidirectional"))
    )
    (net (code "110") (name "Net-(B$14-PadHF)") (class "Default")
      (node (ref "B$14") (pin "HF") (pinfunction "HF_HF") (pintype "bidirectional"))
      (node (ref "S$11") (pin "1") (pinfunction "1_1") (pintype "passive"))
    )
    (net (code "111") (name "Net-(B$14-PadOUT)") (class "Default")
      (node (ref "B$14") (pin "OUT") (pinfunction "OUT_OUT") (pintype "bidirectional"))
      (node (ref "U$1") (pin "RF$15_G5") (pinfunction "RF$15_G5_RF$15_G5") (pintype "bidirectional"))
    )
    (net (code "112") (name "Net-(B$15-PadHF)") (class "Default")
      (node (ref "B$15") (pin "HF") (pinfunction "HF_HF") (pintype "bidirectional"))
      (node (ref "S$12") (pin "1") (pinfunction "1_1") (pintype "passive"))
    )
    (net (code "113") (name "Net-(B$15-PadOUT)") (class "Default")
      (node (ref "B$15") (pin "OUT") (pinfunction "OUT_OUT") (pintype "bidirectional"))
      (node (ref "U$1") (pin "RF$16_G6") (pinfunction "RF$16_G6_RF$16_G6") (pintype "bidirectional"))
    )
    (net (code "114") (name "Net-(B$16-PadHF)") (class "Default")
      (node (ref "B$16") (pin "HF") (pinfunction "HF_HF") (pintype "bidirectional"))
      (node (ref "S$13") (pin "1") (pinfunction "1_1") (pintype "passive"))
    )
    (net (code "115") (name "Net-(B$16-PadOUT)") (class "Default")
      (node (ref "B$16") (pin "OUT") (pinfunction "OUT_OUT") (pintype "bidirectional"))
      (node (ref "U$1") (pin "RF$20_G7") (pinfunction "RF$20_G7_RF$20_G7") (pintype "bidirectional"))
    )
    (net (code "116") (name "Net-(B$17-PadHF)") (class "Default")
      (node (ref "B$17") (pin "HF") (pinfunction "HF_HF") (pintype "bidirectional"))
      (node (ref "S$14") (pin "1") (pinfunction "1_1") (pintype "passive"))
    )
    (net (code "117") (name "Net-(B$17-PadOUT)") (class "Default")
      (node (ref "B$17") (pin "OUT") (pinfunction "OUT_OUT") (pintype "bidirectional"))
      (node (ref "U$1") (pin "RF$21_G8") (pinfunction "RF$21_G8_RF$21_G8") (pintype "bidirectional"))
    )
    (net (code "118") (name "Net-(B$18-PadHF)") (class "Default")
      (node (ref "B$18") (pin "HF") (pinfunction "HF_HF") (pintype "bidirectional"))
      (node (ref "S$3") (pin "1") (pinfunction "1_1") (pintype "passive"))
    )
    (net (code "119") (name "Net-(B$18-PadOUT)") (class "Default")
      (node (ref "B$18") (pin "OUT") (pinfunction "OUT_OUT") (pintype "bidirectional"))
      (node (ref "U$1") (pin "RF$28_G10") (pinfunction "RF$28_G10_RF$28_G10") (pintype "bidirectional"))
    )
    (net (code "120") (name "Net-(B$19-PadHF)") (class "Default")
      (node (ref "B$19") (pin "HF") (pinfunction "HF_HF") (pintype "bidirectional"))
      (node (ref "S$4") (pin "1") (pinfunction "1_1") (pintype "passive"))
    )
    (net (code "121") (name "Net-(B$19-PadOUT)") (class "Default")
      (node (ref "B$19") (pin "OUT") (pinfunction "OUT_OUT") (pintype "bidirectional"))
      (node (ref "U$1") (pin "RF$32_G11") (pinfunction "RF$32_G11_RF$32_G11") (pintype "bidirectional"))
    )
    (net (code "122") (name "Net-(B$20-PadHF)") (class "Default")
      (node (ref "B$20") (pin "HF") (pinfunction "HF_HF") (pintype "bidirectional"))
      (node (ref "S$6") (pin "1") (pinfunction "1_1") (pintype "passive"))
    )
    (net (code "123") (name "Net-(B$20-PadOUT)") (class "Default")
      (node (ref "B$20") (pin "OUT") (pinfunction "OUT_OUT") (pintype "bidirectional"))
      (node (ref "U$1") (pin "RF$33_G12") (pinfunction "RF$33_G12_RF$33_G12") (pintype "bidirectional"))
    )
    (net (code "124") (name "Net-(B$21-PadHF)") (class "Default")
      (node (ref "B$21") (pin "HF") (pinfunction "HF_HF") (pintype "bidirectional"))
      (node (ref "S$7") (pin "1") (pinfunction "1_1") (pintype "passive"))
    )
    (net (code "125") (name "Net-(B$21-PadOUT)") (class "Default")
      (node (ref "B$21") (pin "OUT") (pinfunction "OUT_OUT") (pintype "bidirectional"))
      (node (ref "U$1") (pin "RF$39_G13") (pinfunction "RF$39_G13_RF$39_G13") (pintype "bidirectional"))
    )
    (net (code "126") (name "Net-(B$22-PadHF)") (class "Default")
      (node (ref "B$22") (pin "HF") (pinfunction "HF_HF") (pintype "bidirectional"))
      (node (ref "S$15") (pin "1") (pinfunction "1_1") (pintype "passive"))
    )
    (net (code "127") (name "Net-(B$22-PadOUT)") (class "Default")
      (node (ref "B$22") (pin "OUT") (pinfunction "OUT_OUT") (pintype "bidirectional"))
      (node (ref "U$1") (pin "RF$40_G14") (pinfunction "RF$40_G14_RF$40_G14") (pintype "bidirectional"))
    )
    (net (code "128") (name "Net-(B$23-PadHF)") (class "Default")
      (node (ref "B$23") (pin "HF") (pinfunction "HF_HF") (pintype "bidirectional"))
      (node (ref "S$16") (pin "1") (pinfunction "1_1") (pintype "passive"))
    )
    (net (code "129") (name "Net-(B$23-PadOUT)") (class "Default")
      (node (ref "B$23") (pin "OUT") (pinfunction "OUT_OUT") (pintype "bidirectional"))
      (node (ref "U$1") (pin "RF$44_G15") (pinfunction "RF$44_G15_RF$44_G15") (pintype "bidirectional"))
    )
    (net (code "130") (name "Net-(B$24-PadHF)") (class "Default")
      (node (ref "B$24") (pin "HF") (pinfunction "HF_HF") (pintype "bidirectional"))
      (node (ref "S$17") (pin "1") (pinfunction "1_1") (pintype "passive"))
    )
    (net (code "131") (name "Net-(B$24-PadOUT)") (class "Default")
      (node (ref "B$24") (pin "OUT") (pinfunction "OUT_OUT") (pintype "bidirectional"))
      (node (ref "U$1") (pin "RF$45_G16") (pinfunction "RF$45_G16_RF$45_G16") (pintype "bidirectional"))
    )
    (net (code "132") (name "Net-(U$2-2)") (class "Default")
      (node (ref "B$5") (pin "OUT") (pinfunction "OUT_OUT") (pintype "bidirectional"))
      (node (ref "U$2") (pin "OUT1") (pinfunction "2_OUT1") (pintype "passive"))
      (node (ref "U$33") (pin "OUT") (pinfunction "2_OUT") (pintype "passive"))
    )
    (net (code "133") (name "Net-(U$33-1)") (class "Default")
      (node (ref "L$6") (pin "IN") (pinfunction "IN_IN") (pintype "passive"))
      (node (ref "U$33") (pin "IN") (pinfunction "1_IN") (pintype "passive"))
    )
    (net (code "134") (name "unconnected-(U$1-PadRF$GND)") (class "Default")
      (node (ref "U$1") (pin "RF$GND") (pinfunction "RF$GND_RF$GND") (pintype "bidirectional"))
    )
    (net (code "135") (name "unconnected-(U$1-PadRF$GND1)") (class "Default")
      (node (ref "U$1") (pin "RF$GND1") (pinfunction "RF$GND1_RF$GND1") (pintype "bidirectional"))
    )
    (net (code "136") (name "unconnected-(U$1-PadRF$GND2)") (class "Default")
      (node (ref "U$1") (pin "RF$GND2") (pinfunction "RF$GND2_RF$GND2") (pintype "bidirectional"))
    )
    (net (code "137") (name "unconnected-(U$1-PadRF$GND3)") (class "Default")
      (node (ref "U$1") (pin "RF$GND3") (pinfunction "RF$GND3_RF$GND3") (pintype "bidirectional"))
    )
    (net (code "138") (name "unconnected-(U$1-PadRF$GND4)") (class "Default")
      (node (ref "U$1") (pin "RF$GND4") (pinfunction "RF$GND4_RF$GND4") (pintype "bidirectional"))
    )
    (net (code "139") (name "unconnected-(U$1-PadRF$GND5)") (class "Default")
      (node (ref "U$1") (pin "RF$GND5") (pinfunction "RF$GND5_RF$GND5") (pintype "bidirectional"))
    )
    (net (code "140") (name "unconnected-(U$1-PadRF$GND6)") (class "Default")
      (node (ref "U$1") (pin "RF$GND6") (pinfunction "RF$GND6_RF$GND6") (pintype "bidirectional"))
    )
    (net (code "141") (name "unconnected-(U$1-PadRF$GND7)") (class "Default")
      (node (ref "U$1") (pin "RF$GND7") (pinfunction "RF$GND7_RF$GND7") (pintype "bidirectional"))
    )
  )
)
